# ProDoc_Custom_Keyboard_2025-10-23_RV1.net
KiCad netlist of a schematic drawn in EasyEDA Pro
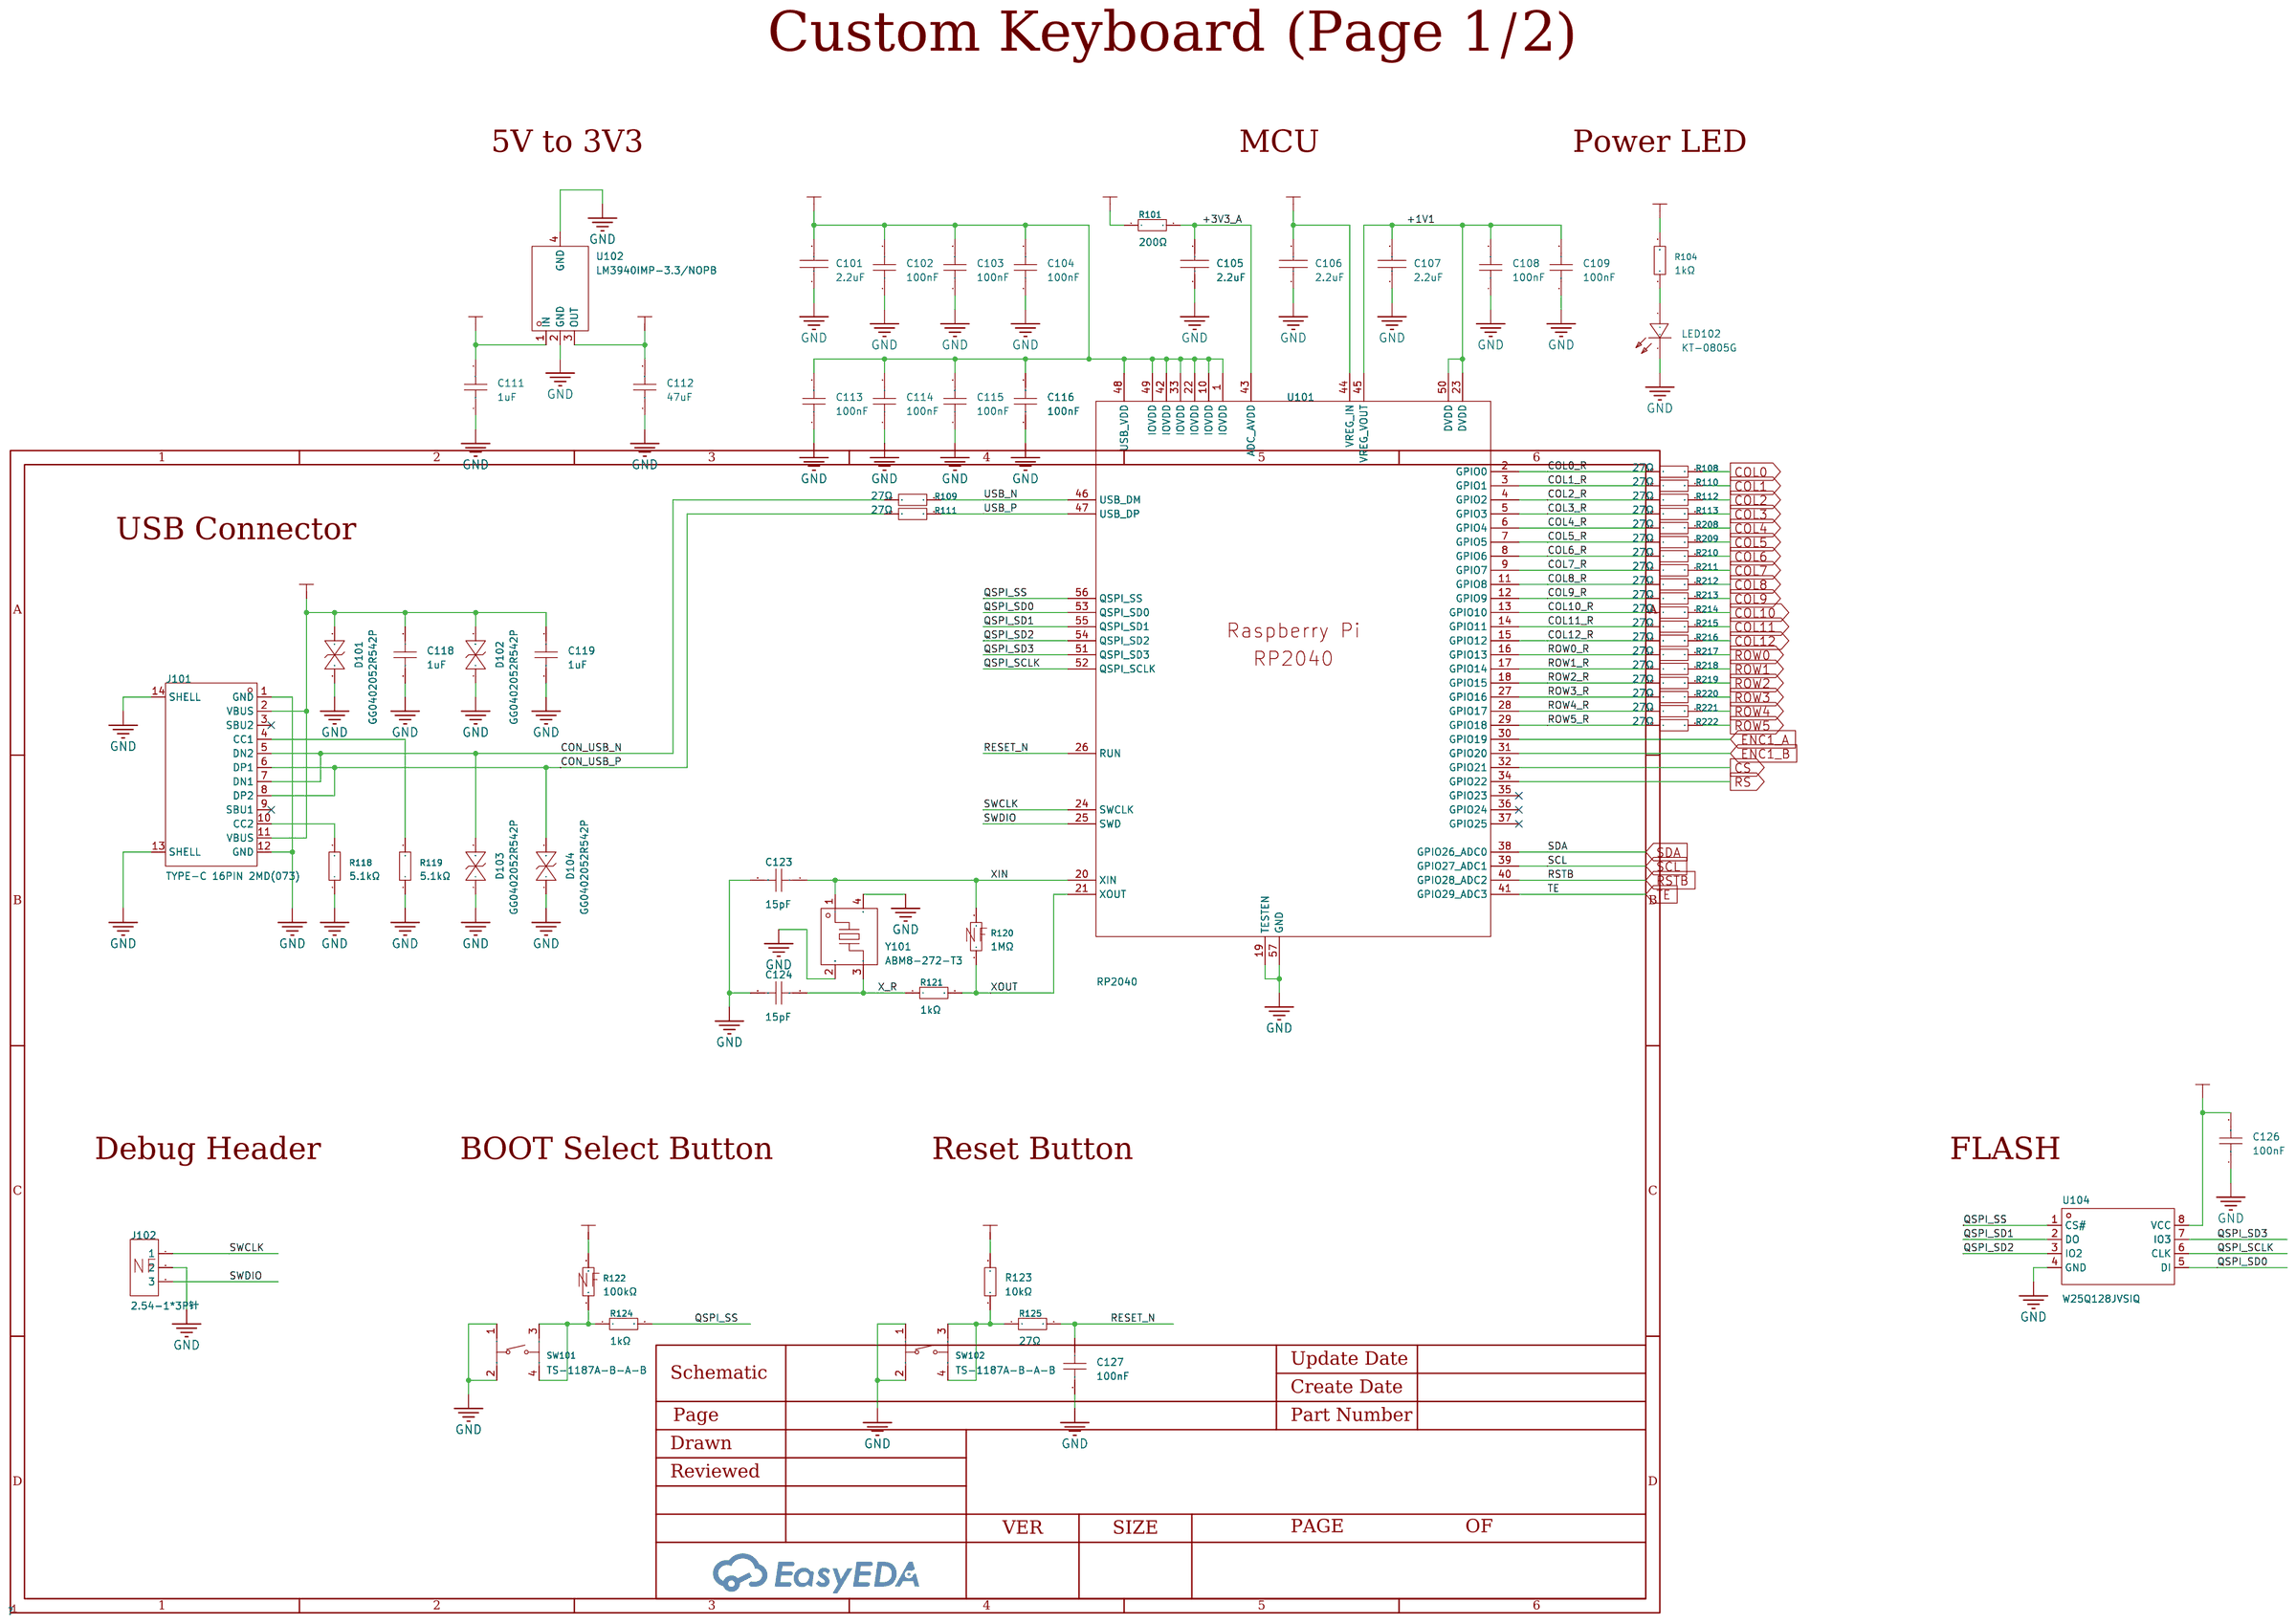
[diagram p0: MCU]
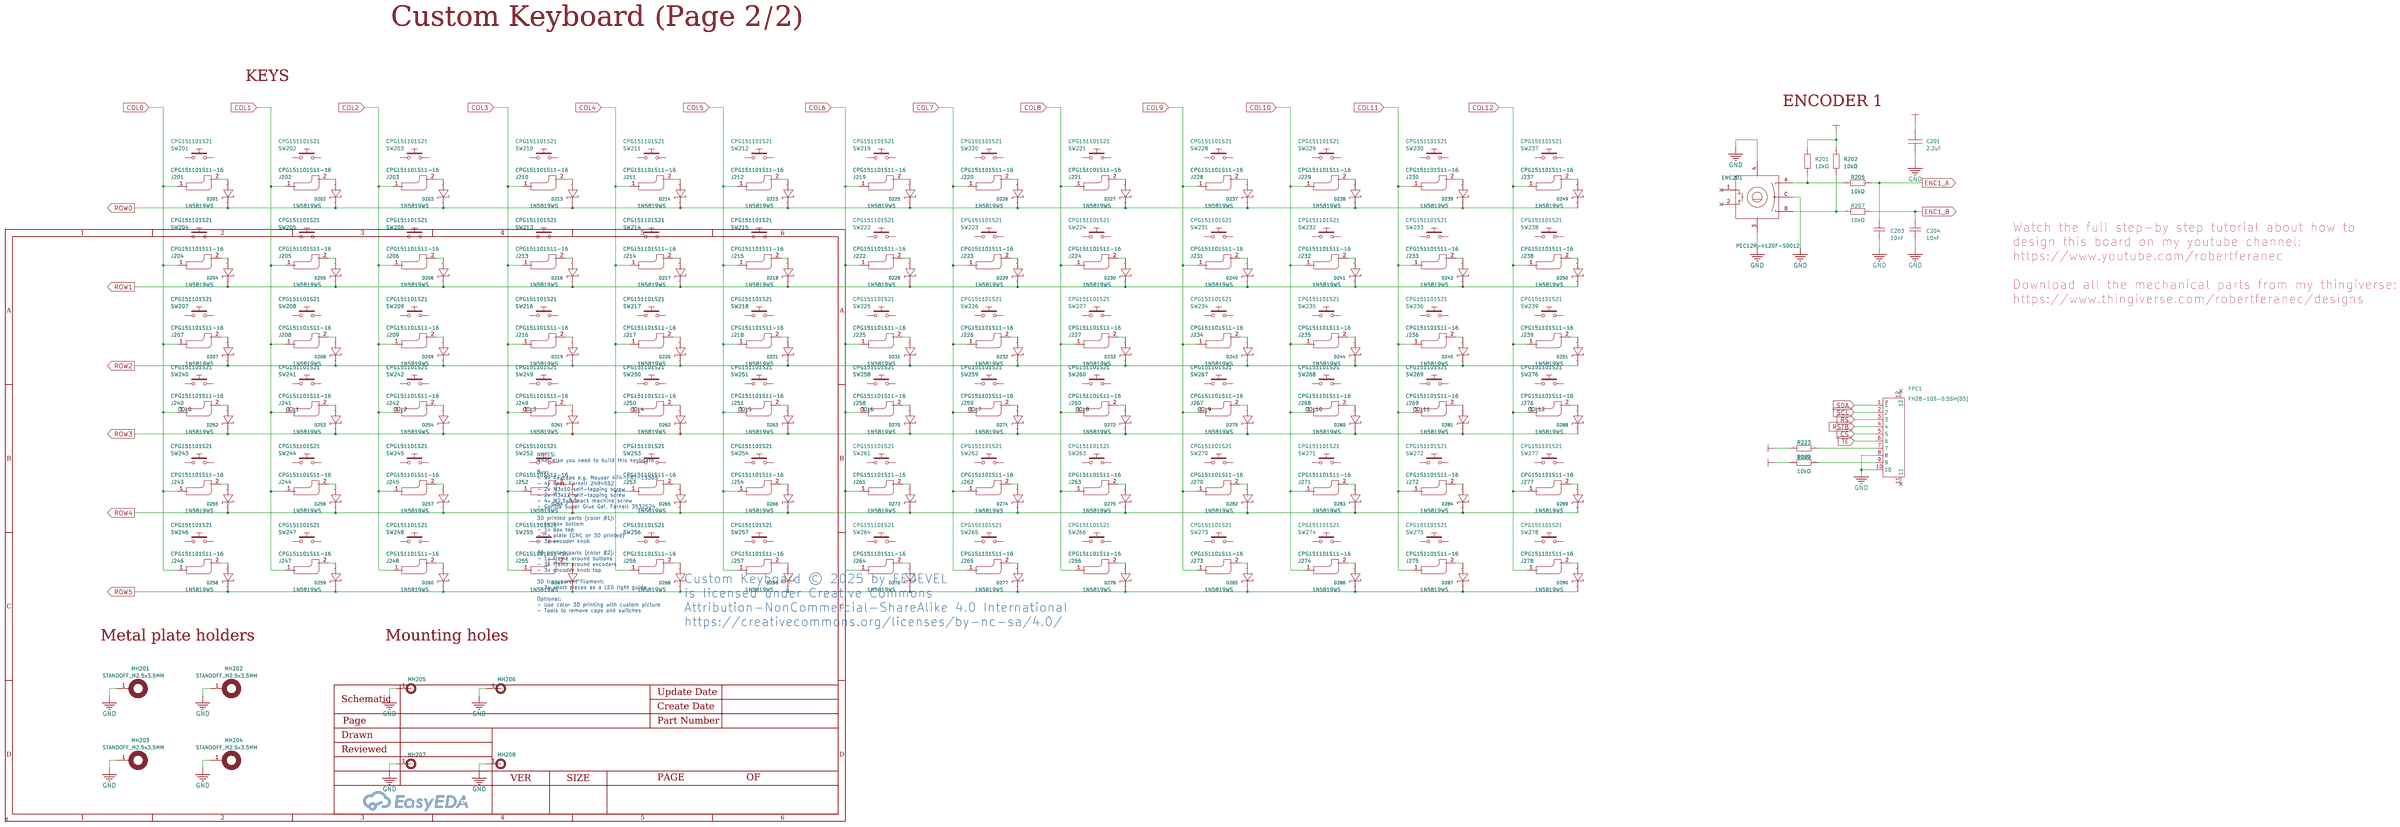
[diagram p1: OTHER]

(export (version "E")
  (design (tool "Eeschema 10.0.6"))
  (components
    (comp (ref "C101")
      (value "2.2uF")
      (footprint "easyedapro:C0402")
      (fields
        (field (name "Manufacturer Part") "CL05A225MQ5NSNC")
        (field (name "Manufacturer") "SAMSUNG(三星)")
      )
      (libsource (lib "easyedapro") (part "CL05A225MQ5NSNC"))
    )
    (comp (ref "C102")
      (value "100nF")
      (footprint "easyedapro:C0402")
      (fields
        (field (name "Manufacturer Part") "CL05B104KO5NNNC")
        (field (name "Manufacturer") "SAMSUNG(三星)")
      )
      (libsource (lib "easyedapro") (part "CL05B104KO5NNNC"))
    )
    (comp (ref "C103")
      (value "100nF")
      (footprint "easyedapro:C0402")
      (fields
        (field (name "Manufacturer Part") "CL05B104KO5NNNC")
        (field (name "Manufacturer") "SAMSUNG(三星)")
      )
      (libsource (lib "easyedapro") (part "CL05B104KO5NNNC"))
    )
    (comp (ref "C104")
      (value "100nF")
      (footprint "easyedapro:C0402")
      (fields
        (field (name "Manufacturer Part") "CL05B104KO5NNNC")
        (field (name "Manufacturer") "SAMSUNG(三星)")
      )
      (libsource (lib "easyedapro") (part "CL05B104KO5NNNC"))
    )
    (comp (ref "C105")
      (value "2.2uF")
      (footprint "easyedapro:C0402")
      (fields
        (field (name "Manufacturer Part") "CL05A225MQ5NSNC")
        (field (name "Manufacturer") "SAMSUNG(三星)")
      )
      (libsource (lib "easyedapro") (part "CL05A225MQ5NSNC"))
    )
    (comp (ref "C106")
      (value "2.2uF")
      (footprint "easyedapro:C0402")
      (fields
        (field (name "Manufacturer Part") "CL05A225MQ5NSNC")
        (field (name "Manufacturer") "SAMSUNG(三星)")
      )
      (libsource (lib "easyedapro") (part "CL05A225MQ5NSNC"))
    )
    (comp (ref "C107")
      (value "2.2uF")
      (footprint "easyedapro:C0402")
      (fields
        (field (name "Manufacturer Part") "CL05A225MQ5NSNC")
        (field (name "Manufacturer") "SAMSUNG(三星)")
      )
      (libsource (lib "easyedapro") (part "CL05A225MQ5NSNC"))
    )
    (comp (ref "C108")
      (value "100nF")
      (footprint "easyedapro:C0402")
      (fields
        (field (name "Manufacturer Part") "CL05B104KO5NNNC")
        (field (name "Manufacturer") "SAMSUNG(三星)")
      )
      (libsource (lib "easyedapro") (part "CL05B104KO5NNNC"))
    )
    (comp (ref "C109")
      (value "100nF")
      (footprint "easyedapro:C0402")
      (fields
        (field (name "Manufacturer Part") "CL05B104KO5NNNC")
        (field (name "Manufacturer") "SAMSUNG(三星)")
      )
      (libsource (lib "easyedapro") (part "CL05B104KO5NNNC"))
    )
    (comp (ref "C111")
      (value "1uF")
      (footprint "easyedapro:C0402")
      (fields
        (field (name "Manufacturer Part") "CL05A105KA5NQNC")
        (field (name "Manufacturer") "SAMSUNG(三星)")
      )
      (libsource (lib "easyedapro") (part "CL05A105KA5NQNC"))
    )
    (comp (ref "C112")
      (value "47uF")
      (footprint "easyedapro:C1206")
      (fields
        (field (name "Manufacturer Part") "CL31A476MPHNNNE")
        (field (name "Manufacturer") "SAMSUNG(三星)")
      )
      (libsource (lib "easyedapro") (part "CL31A476MPHNNNE"))
    )
    (comp (ref "C113")
      (value "100nF")
      (footprint "easyedapro:C0402")
      (fields
        (field (name "Manufacturer Part") "CL05B104KO5NNNC")
        (field (name "Manufacturer") "SAMSUNG(三星)")
      )
      (libsource (lib "easyedapro") (part "CL05B104KO5NNNC"))
    )
    (comp (ref "C114")
      (value "100nF")
      (footprint "easyedapro:C0402")
      (fields
        (field (name "Manufacturer Part") "CL05B104KO5NNNC")
        (field (name "Manufacturer") "SAMSUNG(三星)")
      )
      (libsource (lib "easyedapro") (part "CL05B104KO5NNNC"))
    )
    (comp (ref "C115")
      (value "100nF")
      (footprint "easyedapro:C0402")
      (fields
        (field (name "Manufacturer Part") "CL05B104KO5NNNC")
        (field (name "Manufacturer") "SAMSUNG(三星)")
      )
      (libsource (lib "easyedapro") (part "CL05B104KO5NNNC"))
    )
    (comp (ref "C116")
      (value "100nF")
      (footprint "easyedapro:C0402")
      (fields
        (field (name "Manufacturer Part") "CL05B104KO5NNNC")
        (field (name "Manufacturer") "SAMSUNG(三星)")
      )
      (libsource (lib "easyedapro") (part "CL05B104KO5NNNC"))
    )
    (comp (ref "C118")
      (value "1uF")
      (footprint "easyedapro:C0402")
      (fields
        (field (name "Manufacturer Part") "CL05A105KA5NQNC")
        (field (name "Manufacturer") "SAMSUNG(三星)")
      )
      (libsource (lib "easyedapro") (part "CL05A105KA5NQNC"))
    )
    (comp (ref "C119")
      (value "1uF")
      (footprint "easyedapro:C0402")
      (fields
        (field (name "Manufacturer Part") "CL05A105KA5NQNC")
        (field (name "Manufacturer") "SAMSUNG(三星)")
      )
      (libsource (lib "easyedapro") (part "CL05A105KA5NQNC"))
    )
    (comp (ref "C123")
      (value "15pF")
      (footprint "easyedapro:C0402")
      (fields
        (field (name "Manufacturer Part") "CL05C150JB5NNNC")
        (field (name "Manufacturer") "SAMSUNG(三星)")
      )
      (libsource (lib "easyedapro") (part "CL05C150JB5NNNC"))
    )
    (comp (ref "C124")
      (value "15pF")
      (footprint "easyedapro:C0402")
      (fields
        (field (name "Manufacturer Part") "CL05C150JB5NNNC")
        (field (name "Manufacturer") "SAMSUNG(三星)")
      )
      (libsource (lib "easyedapro") (part "CL05C150JB5NNNC"))
    )
    (comp (ref "C126")
      (value "100nF")
      (footprint "easyedapro:C0402")
      (fields
        (field (name "Manufacturer Part") "CL05B104KO5NNNC")
        (field (name "Manufacturer") "SAMSUNG(三星)")
      )
      (libsource (lib "easyedapro") (part "CL05B104KO5NNNC"))
    )
    (comp (ref "C127")
      (value "100nF")
      (footprint "easyedapro:C0402")
      (fields
        (field (name "Manufacturer Part") "CL05B104KO5NNNC")
        (field (name "Manufacturer") "SAMSUNG(三星)")
      )
      (libsource (lib "easyedapro") (part "CL05B104KO5NNNC"))
    )
    (comp (ref "D101")
      (value "GG0402052R542P")
      (footprint "easyedapro:D0402-BI")
      (fields (field (name "Manufacturer") "Kyocera AVX"))
      (libsource (lib "easyedapro") (part "GG0402052R542P"))
    )
    (comp (ref "D102")
      (value "GG0402052R542P")
      (footprint "easyedapro:D0402-BI")
      (fields (field (name "Manufacturer") "Kyocera AVX"))
      (libsource (lib "easyedapro") (part "GG0402052R542P"))
    )
    (comp (ref "D103")
      (value "GG0402052R542P")
      (footprint "easyedapro:D0402-BI")
      (fields (field (name "Manufacturer") "Kyocera AVX"))
      (libsource (lib "easyedapro") (part "GG0402052R542P"))
    )
    (comp (ref "D104")
      (value "GG0402052R542P")
      (footprint "easyedapro:D0402-BI")
      (fields (field (name "Manufacturer") "Kyocera AVX"))
      (libsource (lib "easyedapro") (part "GG0402052R542P"))
    )
    (comp (ref "J101")
      (value "TYPE-C 16PIN 2MD(073)")
      (footprint "easyedapro:USB-C-SMD_TYPE-C-6PIN-2MD-073")
      (fields (field (name "Manufacturer") "SHOU HAN(首韩)"))
      (libsource (lib "easyedapro") (part "TYPE-C 16PIN 2MD(073)"))
    )
    (comp (ref "J102")
      (value "2.54-1*3P针")
      (footprint "easyedapro:HDR-TH_3P-P2.54-V-M-1")
      (fields (field (name "Manufacturer") "BOOMELE(博穆精密)"))
      (libsource (lib "easyedapro") (part "Header-Male-2.54_1x3"))
    )
    (comp (ref "LED102")
      (value "KT-0805G")
      (footprint "easyedapro:LED0805-R-RD")
      (fields (field (name "Manufacturer") "KENTO"))
      (libsource (lib "easyedapro") (part "0805G (Green)"))
    )
    (comp (ref "R101")
      (value "200Ω")
      (footprint "easyedapro:R0402")
      (fields
        (field (name "Manufacturer Part") "0402WGF2000TCE")
        (field (name "Manufacturer") "UNI-ROYAL(厚声)")
      )
      (libsource (lib "easyedapro") (part "0402WGF2000TCE"))
    )
    (comp (ref "R104")
      (value "1kΩ")
      (footprint "easyedapro:R0402")
      (fields
        (field (name "Manufacturer Part") "0402WGF1001TCE")
        (field (name "Manufacturer") "UNI-ROYAL(厚声)")
      )
      (libsource (lib "easyedapro") (part "0402WGF1001TCE"))
    )
    (comp (ref "R108")
      (value "27Ω")
      (footprint "easyedapro:R0402")
      (fields
        (field (name "Manufacturer Part") "0402WGF270JTCE")
        (field (name "Manufacturer") "UNI-ROYAL(厚声)")
      )
      (libsource (lib "easyedapro") (part "0402WGF270JTCE"))
    )
    (comp (ref "R109")
      (value "27Ω")
      (footprint "easyedapro:R0402")
      (fields
        (field (name "Manufacturer Part") "0402WGF270JTCE")
        (field (name "Manufacturer") "UNI-ROYAL(厚声)")
      )
      (libsource (lib "easyedapro") (part "0402WGF270JTCE"))
    )
    (comp (ref "R110")
      (value "27Ω")
      (footprint "easyedapro:R0402")
      (fields
        (field (name "Manufacturer Part") "0402WGF270JTCE")
        (field (name "Manufacturer") "UNI-ROYAL(厚声)")
      )
      (libsource (lib "easyedapro") (part "0402WGF270JTCE"))
    )
    (comp (ref "R111")
      (value "27Ω")
      (footprint "easyedapro:R0402")
      (fields
        (field (name "Manufacturer Part") "0402WGF270JTCE")
        (field (name "Manufacturer") "UNI-ROYAL(厚声)")
      )
      (libsource (lib "easyedapro") (part "0402WGF270JTCE"))
    )
    (comp (ref "R112")
      (value "27Ω")
      (footprint "easyedapro:R0402")
      (fields
        (field (name "Manufacturer Part") "0402WGF270JTCE")
        (field (name "Manufacturer") "UNI-ROYAL(厚声)")
      )
      (libsource (lib "easyedapro") (part "0402WGF270JTCE"))
    )
    (comp (ref "R113")
      (value "27Ω")
      (footprint "easyedapro:R0402")
      (fields
        (field (name "Manufacturer Part") "0402WGF270JTCE")
        (field (name "Manufacturer") "UNI-ROYAL(厚声)")
      )
      (libsource (lib "easyedapro") (part "0402WGF270JTCE"))
    )
    (comp (ref "R118")
      (value "5.1kΩ")
      (footprint "easyedapro:R0402")
      (fields
        (field (name "Manufacturer Part") "0402WGF5101TCE")
        (field (name "Manufacturer") "UNI-ROYAL(厚声)")
      )
      (libsource (lib "easyedapro") (part "0402WGF5101TCE"))
    )
    (comp (ref "R119")
      (value "5.1kΩ")
      (footprint "easyedapro:R0402")
      (fields
        (field (name "Manufacturer Part") "0402WGF5101TCE")
        (field (name "Manufacturer") "UNI-ROYAL(厚声)")
      )
      (libsource (lib "easyedapro") (part "0402WGF5101TCE"))
    )
    (comp (ref "R120")
      (value "1MΩ")
      (footprint "easyedapro:R0402")
      (fields
        (field (name "Manufacturer Part") "0402WGF1004TCE")
        (field (name "Manufacturer") "UNI-ROYAL(厚声)")
      )
      (libsource (lib "easyedapro") (part "0402WGF1004TCE"))
    )
    (comp (ref "R121")
      (value "1kΩ")
      (footprint "easyedapro:R0402")
      (fields
        (field (name "Manufacturer Part") "0402WGF1001TCE")
        (field (name "Manufacturer") "UNI-ROYAL(厚声)")
      )
      (libsource (lib "easyedapro") (part "0402WGF1001TCE"))
    )
    (comp (ref "R122")
      (value "100kΩ")
      (footprint "easyedapro:R0402")
      (fields
        (field (name "Manufacturer Part") "0402WGF1003TCE")
        (field (name "Manufacturer") "UNI-ROYAL(厚声)")
      )
      (libsource (lib "easyedapro") (part "0402WGF1003TCE"))
    )
    (comp (ref "R123")
      (value "10kΩ")
      (footprint "easyedapro:R0402")
      (fields
        (field (name "Manufacturer Part") "0402WGF1002TCE")
        (field (name "Manufacturer") "UNI-ROYAL(厚声)")
      )
      (libsource (lib "easyedapro") (part "0402WGF1002TCE"))
    )
    (comp (ref "R124")
      (value "1kΩ")
      (footprint "easyedapro:R0402")
      (fields
        (field (name "Manufacturer Part") "0402WGF1001TCE")
        (field (name "Manufacturer") "UNI-ROYAL(厚声)")
      )
      (libsource (lib "easyedapro") (part "0402WGF1001TCE"))
    )
    (comp (ref "R125")
      (value "27Ω")
      (footprint "easyedapro:R0402")
      (fields
        (field (name "Manufacturer Part") "0402WGF270JTCE")
        (field (name "Manufacturer") "UNI-ROYAL(厚声)")
      )
      (libsource (lib "easyedapro") (part "0402WGF270JTCE"))
    )
    (comp (ref "R208")
      (value "27Ω")
      (footprint "easyedapro:R0402")
      (fields
        (field (name "Manufacturer Part") "0402WGF270JTCE")
        (field (name "Manufacturer") "UNI-ROYAL(厚声)")
      )
      (libsource (lib "easyedapro") (part "0402WGF270JTCE"))
    )
    (comp (ref "R209")
      (value "27Ω")
      (footprint "easyedapro:R0402")
      (fields
        (field (name "Manufacturer Part") "0402WGF270JTCE")
        (field (name "Manufacturer") "UNI-ROYAL(厚声)")
      )
      (libsource (lib "easyedapro") (part "0402WGF270JTCE"))
    )
    (comp (ref "R210")
      (value "27Ω")
      (footprint "easyedapro:R0402")
      (fields
        (field (name "Manufacturer Part") "0402WGF270JTCE")
        (field (name "Manufacturer") "UNI-ROYAL(厚声)")
      )
      (libsource (lib "easyedapro") (part "0402WGF270JTCE"))
    )
    (comp (ref "R211")
      (value "27Ω")
      (footprint "easyedapro:R0402")
      (fields
        (field (name "Manufacturer Part") "0402WGF270JTCE")
        (field (name "Manufacturer") "UNI-ROYAL(厚声)")
      )
      (libsource (lib "easyedapro") (part "0402WGF270JTCE"))
    )
    (comp (ref "R212")
      (value "27Ω")
      (footprint "easyedapro:R0402")
      (fields
        (field (name "Manufacturer Part") "0402WGF270JTCE")
        (field (name "Manufacturer") "UNI-ROYAL(厚声)")
      )
      (libsource (lib "easyedapro") (part "0402WGF270JTCE"))
    )
    (comp (ref "R213")
      (value "27Ω")
      (footprint "easyedapro:R0402")
      (fields
        (field (name "Manufacturer Part") "0402WGF270JTCE")
        (field (name "Manufacturer") "UNI-ROYAL(厚声)")
      )
      (libsource (lib "easyedapro") (part "0402WGF270JTCE"))
    )
    (comp (ref "R214")
      (value "27Ω")
      (footprint "easyedapro:R0402")
      (fields
        (field (name "Manufacturer Part") "0402WGF270JTCE")
        (field (name "Manufacturer") "UNI-ROYAL(厚声)")
      )
      (libsource (lib "easyedapro") (part "0402WGF270JTCE"))
    )
    (comp (ref "R215")
      (value "27Ω")
      (footprint "easyedapro:R0402")
      (fields
        (field (name "Manufacturer Part") "0402WGF270JTCE")
        (field (name "Manufacturer") "UNI-ROYAL(厚声)")
      )
      (libsource (lib "easyedapro") (part "0402WGF270JTCE"))
    )
    (comp (ref "R216")
      (value "27Ω")
      (footprint "easyedapro:R0402")
      (fields
        (field (name "Manufacturer Part") "0402WGF270JTCE")
        (field (name "Manufacturer") "UNI-ROYAL(厚声)")
      )
      (libsource (lib "easyedapro") (part "0402WGF270JTCE"))
    )
    (comp (ref "R217")
      (value "27Ω")
      (footprint "easyedapro:R0402")
      (fields
        (field (name "Manufacturer Part") "0402WGF270JTCE")
        (field (name "Manufacturer") "UNI-ROYAL(厚声)")
      )
      (libsource (lib "easyedapro") (part "0402WGF270JTCE"))
    )
    (comp (ref "R218")
      (value "27Ω")
      (footprint "easyedapro:R0402")
      (fields
        (field (name "Manufacturer Part") "0402WGF270JTCE")
        (field (name "Manufacturer") "UNI-ROYAL(厚声)")
      )
      (libsource (lib "easyedapro") (part "0402WGF270JTCE"))
    )
    (comp (ref "R219")
      (value "27Ω")
      (footprint "easyedapro:R0402")
      (fields
        (field (name "Manufacturer Part") "0402WGF270JTCE")
        (field (name "Manufacturer") "UNI-ROYAL(厚声)")
      )
      (libsource (lib "easyedapro") (part "0402WGF270JTCE"))
    )
    (comp (ref "R220")
      (value "27Ω")
      (footprint "easyedapro:R0402")
      (fields
        (field (name "Manufacturer Part") "0402WGF270JTCE")
        (field (name "Manufacturer") "UNI-ROYAL(厚声)")
      )
      (libsource (lib "easyedapro") (part "0402WGF270JTCE"))
    )
    (comp (ref "R221")
      (value "27Ω")
      (footprint "easyedapro:R0402")
      (fields
        (field (name "Manufacturer Part") "0402WGF270JTCE")
        (field (name "Manufacturer") "UNI-ROYAL(厚声)")
      )
      (libsource (lib "easyedapro") (part "0402WGF270JTCE"))
    )
    (comp (ref "R222")
      (value "27Ω")
      (footprint "easyedapro:R0402")
      (fields
        (field (name "Manufacturer Part") "0402WGF270JTCE")
        (field (name "Manufacturer") "UNI-ROYAL(厚声)")
      )
      (libsource (lib "easyedapro") (part "0402WGF270JTCE"))
    )
    (comp (ref "SW101")
      (value "TS-1187A-B-A-B")
      (footprint "easyedapro:SW-SMD_4P-L5.1-W5.1-P3.70-LS6.5-TL-2")
      (fields (field (name "Manufacturer") "XKB Connectivity(中国星坤)"))
      (libsource (lib "easyedapro") (part "TS-1187A-B-A-B"))
    )
    (comp (ref "SW102")
      (value "TS-1187A-B-A-B")
      (footprint "easyedapro:SW-SMD_4P-L5.1-W5.1-P3.70-LS6.5-TL-2")
      (fields (field (name "Manufacturer") "XKB Connectivity(中国星坤)"))
      (libsource (lib "easyedapro") (part "TS-1187A-B-A-B"))
    )
    (comp (ref "U101")
      (value "RP2040")
      (footprint "easyedapro:LQFN-56_L7.0-W7.0-P0.4-EP_1")
      (fields (field (name "Manufacturer") "Raspberry Pi(树莓派)"))
      (libsource (lib "easyedapro") (part "RP2040_C2040_RF_v1.0"))
    )
    (comp (ref "U102")
      (value "LM3940IMP-3.3/NOPB")
      (footprint "easyedapro:SOT-223_L6.5-W3.5-P2.30-LS7.0-BR")
      (fields (field (name "Manufacturer") "TI(德州仪器)"))
      (libsource (lib "easyedapro") (part "LM3940IMP-3.3/NOPB"))
    )
    (comp (ref "U104")
      (value "W25Q128JVSIQ")
      (footprint "easyedapro:SOIC-8_L5.3-W5.3-P1.27-LS8.0-BL")
      (fields (field (name "Manufacturer") "WINBOND(华邦)"))
      (libsource (lib "easyedapro") (part "W25Q128JVSIQTR"))
    )
    (comp (ref "Y101")
      (value "ABM8-272-T3")
      (footprint "easyedapro:CRYSTAL-SMD_4P-L3.2-W2.5-BL")
      (fields (field (name "Manufacturer") "ABRACON"))
      (libsource (lib "easyedapro") (part "ABM8-272-T3_C20625731"))
    )
    (comp (ref "C201")
      (value "2.2uF")
      (footprint "easyedapro:C0402")
      (fields
        (field (name "Manufacturer Part") "CL05A225MQ5NSNC")
        (field (name "Manufacturer") "SAMSUNG(三星)")
      )
      (libsource (lib "easyedapro") (part "CL05A225MQ5NSNC"))
    )
    (comp (ref "C203")
      (value "10nF")
      (footprint "easyedapro:C0402")
      (fields
        (field (name "Manufacturer Part") "CL05B103KB5NNNC")
        (field (name "Manufacturer") "SAMSUNG(三星)")
      )
      (libsource (lib "easyedapro") (part "CL05B103KB5NNNC"))
    )
    (comp (ref "C204")
      (value "10nF")
      (footprint "easyedapro:C0402")
      (fields
        (field (name "Manufacturer Part") "CL05B103KB5NNNC")
        (field (name "Manufacturer") "SAMSUNG(三星)")
      )
      (libsource (lib "easyedapro") (part "CL05B103KB5NNNC"))
    )
    (comp (ref "D201")
      (value "1N5819WS")
      (footprint "easyedapro:SOD-323_L1.8-W1.3-LS2.5-RD")
      (description "Forward Voltage (Vf@If):600mV@1A Reverse Voltage (Vr):40V Average Rectified Current (Io):1A")
      (fields (field (name "Manufacturer") "Hottech(合科泰)"))
      (libsource (lib "easyedapro") (part "1N5819WS"))
    )
    (comp (ref "D202")
      (value "1N5819WS")
      (footprint "easyedapro:SOD-323_L1.8-W1.3-LS2.5-RD")
      (description "Forward Voltage (Vf@If):600mV@1A Reverse Voltage (Vr):40V Average Rectified Current (Io):1A")
      (fields (field (name "Manufacturer") "Hottech(合科泰)"))
      (libsource (lib "easyedapro") (part "1N5819WS"))
    )
    (comp (ref "D203")
      (value "1N5819WS")
      (footprint "easyedapro:SOD-323_L1.8-W1.3-LS2.5-RD")
      (description "Forward Voltage (Vf@If):600mV@1A Reverse Voltage (Vr):40V Average Rectified Current (Io):1A")
      (fields (field (name "Manufacturer") "Hottech(合科泰)"))
      (libsource (lib "easyedapro") (part "1N5819WS"))
    )
    (comp (ref "D204")
      (value "1N5819WS")
      (footprint "easyedapro:SOD-323_L1.8-W1.3-LS2.5-RD")
      (description "Forward Voltage (Vf@If):600mV@1A Reverse Voltage (Vr):40V Average Rectified Current (Io):1A")
      (fields (field (name "Manufacturer") "Hottech(合科泰)"))
      (libsource (lib "easyedapro") (part "1N5819WS"))
    )
    (comp (ref "D205")
      (value "1N5819WS")
      (footprint "easyedapro:SOD-323_L1.8-W1.3-LS2.5-RD")
      (description "Forward Voltage (Vf@If):600mV@1A Reverse Voltage (Vr):40V Average Rectified Current (Io):1A")
      (fields (field (name "Manufacturer") "Hottech(合科泰)"))
      (libsource (lib "easyedapro") (part "1N5819WS"))
    )
    (comp (ref "D206")
      (value "1N5819WS")
      (footprint "easyedapro:SOD-323_L1.8-W1.3-LS2.5-RD")
      (description "Forward Voltage (Vf@If):600mV@1A Reverse Voltage (Vr):40V Average Rectified Current (Io):1A")
      (fields (field (name "Manufacturer") "Hottech(合科泰)"))
      (libsource (lib "easyedapro") (part "1N5819WS"))
    )
    (comp (ref "D207")
      (value "1N5819WS")
      (footprint "easyedapro:SOD-323_L1.8-W1.3-LS2.5-RD")
      (description "Forward Voltage (Vf@If):600mV@1A Reverse Voltage (Vr):40V Average Rectified Current (Io):1A")
      (fields (field (name "Manufacturer") "Hottech(合科泰)"))
      (libsource (lib "easyedapro") (part "1N5819WS"))
    )
    (comp (ref "D208")
      (value "1N5819WS")
      (footprint "easyedapro:SOD-323_L1.8-W1.3-LS2.5-RD")
      (description "Forward Voltage (Vf@If):600mV@1A Reverse Voltage (Vr):40V Average Rectified Current (Io):1A")
      (fields (field (name "Manufacturer") "Hottech(合科泰)"))
      (libsource (lib "easyedapro") (part "1N5819WS"))
    )
    (comp (ref "D209")
      (value "1N5819WS")
      (footprint "easyedapro:SOD-323_L1.8-W1.3-LS2.5-RD")
      (description "Forward Voltage (Vf@If):600mV@1A Reverse Voltage (Vr):40V Average Rectified Current (Io):1A")
      (fields (field (name "Manufacturer") "Hottech(合科泰)"))
      (libsource (lib "easyedapro") (part "1N5819WS"))
    )
    (comp (ref "D213")
      (value "1N5819WS")
      (footprint "easyedapro:SOD-323_L1.8-W1.3-LS2.5-RD")
      (description "Forward Voltage (Vf@If):600mV@1A Reverse Voltage (Vr):40V Average Rectified Current (Io):1A")
      (fields (field (name "Manufacturer") "Hottech(合科泰)"))
      (libsource (lib "easyedapro") (part "1N5819WS"))
    )
    (comp (ref "D214")
      (value "1N5819WS")
      (footprint "easyedapro:SOD-323_L1.8-W1.3-LS2.5-RD")
      (description "Forward Voltage (Vf@If):600mV@1A Reverse Voltage (Vr):40V Average Rectified Current (Io):1A")
      (fields (field (name "Manufacturer") "Hottech(合科泰)"))
      (libsource (lib "easyedapro") (part "1N5819WS"))
    )
    (comp (ref "D215")
      (value "1N5819WS")
      (footprint "easyedapro:SOD-323_L1.8-W1.3-LS2.5-RD")
      (description "Forward Voltage (Vf@If):600mV@1A Reverse Voltage (Vr):40V Average Rectified Current (Io):1A")
      (fields (field (name "Manufacturer") "Hottech(合科泰)"))
      (libsource (lib "easyedapro") (part "1N5819WS"))
    )
    (comp (ref "D216")
      (value "1N5819WS")
      (footprint "easyedapro:SOD-323_L1.8-W1.3-LS2.5-RD")
      (description "Forward Voltage (Vf@If):600mV@1A Reverse Voltage (Vr):40V Average Rectified Current (Io):1A")
      (fields (field (name "Manufacturer") "Hottech(合科泰)"))
      (libsource (lib "easyedapro") (part "1N5819WS"))
    )
    (comp (ref "D217")
      (value "1N5819WS")
      (footprint "easyedapro:SOD-323_L1.8-W1.3-LS2.5-RD")
      (description "Forward Voltage (Vf@If):600mV@1A Reverse Voltage (Vr):40V Average Rectified Current (Io):1A")
      (fields (field (name "Manufacturer") "Hottech(合科泰)"))
      (libsource (lib "easyedapro") (part "1N5819WS"))
    )
    (comp (ref "D218")
      (value "1N5819WS")
      (footprint "easyedapro:SOD-323_L1.8-W1.3-LS2.5-RD")
      (description "Forward Voltage (Vf@If):600mV@1A Reverse Voltage (Vr):40V Average Rectified Current (Io):1A")
      (fields (field (name "Manufacturer") "Hottech(合科泰)"))
      (libsource (lib "easyedapro") (part "1N5819WS"))
    )
    (comp (ref "D219")
      (value "1N5819WS")
      (footprint "easyedapro:SOD-323_L1.8-W1.3-LS2.5-RD")
      (description "Forward Voltage (Vf@If):600mV@1A Reverse Voltage (Vr):40V Average Rectified Current (Io):1A")
      (fields (field (name "Manufacturer") "Hottech(合科泰)"))
      (libsource (lib "easyedapro") (part "1N5819WS"))
    )
    (comp (ref "D220")
      (value "1N5819WS")
      (footprint "easyedapro:SOD-323_L1.8-W1.3-LS2.5-RD")
      (description "Forward Voltage (Vf@If):600mV@1A Reverse Voltage (Vr):40V Average Rectified Current (Io):1A")
      (fields (field (name "Manufacturer") "Hottech(合科泰)"))
      (libsource (lib "easyedapro") (part "1N5819WS"))
    )
    (comp (ref "D221")
      (value "1N5819WS")
      (footprint "easyedapro:SOD-323_L1.8-W1.3-LS2.5-RD")
      (description "Forward Voltage (Vf@If):600mV@1A Reverse Voltage (Vr):40V Average Rectified Current (Io):1A")
      (fields (field (name "Manufacturer") "Hottech(合科泰)"))
      (libsource (lib "easyedapro") (part "1N5819WS"))
    )
    (comp (ref "D225")
      (value "1N5819WS")
      (footprint "easyedapro:SOD-323_L1.8-W1.3-LS2.5-RD")
      (description "Forward Voltage (Vf@If):600mV@1A Reverse Voltage (Vr):40V Average Rectified Current (Io):1A")
      (fields (field (name "Manufacturer") "Hottech(合科泰)"))
      (libsource (lib "easyedapro") (part "1N5819WS"))
    )
    (comp (ref "D226")
      (value "1N5819WS")
      (footprint "easyedapro:SOD-323_L1.8-W1.3-LS2.5-RD")
      (description "Forward Voltage (Vf@If):600mV@1A Reverse Voltage (Vr):40V Average Rectified Current (Io):1A")
      (fields (field (name "Manufacturer") "Hottech(合科泰)"))
      (libsource (lib "easyedapro") (part "1N5819WS"))
    )
    (comp (ref "D227")
      (value "1N5819WS")
      (footprint "easyedapro:SOD-323_L1.8-W1.3-LS2.5-RD")
      (description "Forward Voltage (Vf@If):600mV@1A Reverse Voltage (Vr):40V Average Rectified Current (Io):1A")
      (fields (field (name "Manufacturer") "Hottech(合科泰)"))
      (libsource (lib "easyedapro") (part "1N5819WS"))
    )
    (comp (ref "D228")
      (value "1N5819WS")
      (footprint "easyedapro:SOD-323_L1.8-W1.3-LS2.5-RD")
      (description "Forward Voltage (Vf@If):600mV@1A Reverse Voltage (Vr):40V Average Rectified Current (Io):1A")
      (fields (field (name "Manufacturer") "Hottech(合科泰)"))
      (libsource (lib "easyedapro") (part "1N5819WS"))
    )
    (comp (ref "D229")
      (value "1N5819WS")
      (footprint "easyedapro:SOD-323_L1.8-W1.3-LS2.5-RD")
      (description "Forward Voltage (Vf@If):600mV@1A Reverse Voltage (Vr):40V Average Rectified Current (Io):1A")
      (fields (field (name "Manufacturer") "Hottech(合科泰)"))
      (libsource (lib "easyedapro") (part "1N5819WS"))
    )
    (comp (ref "D230")
      (value "1N5819WS")
      (footprint "easyedapro:SOD-323_L1.8-W1.3-LS2.5-RD")
      (description "Forward Voltage (Vf@If):600mV@1A Reverse Voltage (Vr):40V Average Rectified Current (Io):1A")
      (fields (field (name "Manufacturer") "Hottech(合科泰)"))
      (libsource (lib "easyedapro") (part "1N5819WS"))
    )
    (comp (ref "D231")
      (value "1N5819WS")
      (footprint "easyedapro:SOD-323_L1.8-W1.3-LS2.5-RD")
      (description "Forward Voltage (Vf@If):600mV@1A Reverse Voltage (Vr):40V Average Rectified Current (Io):1A")
      (fields (field (name "Manufacturer") "Hottech(合科泰)"))
      (libsource (lib "easyedapro") (part "1N5819WS"))
    )
    (comp (ref "D232")
      (value "1N5819WS")
      (footprint "easyedapro:SOD-323_L1.8-W1.3-LS2.5-RD")
      (description "Forward Voltage (Vf@If):600mV@1A Reverse Voltage (Vr):40V Average Rectified Current (Io):1A")
      (fields (field (name "Manufacturer") "Hottech(合科泰)"))
      (libsource (lib "easyedapro") (part "1N5819WS"))
    )
    (comp (ref "D233")
      (value "1N5819WS")
      (footprint "easyedapro:SOD-323_L1.8-W1.3-LS2.5-RD")
      (description "Forward Voltage (Vf@If):600mV@1A Reverse Voltage (Vr):40V Average Rectified Current (Io):1A")
      (fields (field (name "Manufacturer") "Hottech(合科泰)"))
      (libsource (lib "easyedapro") (part "1N5819WS"))
    )
    (comp (ref "D237")
      (value "1N5819WS")
      (footprint "easyedapro:SOD-323_L1.8-W1.3-LS2.5-RD")
      (description "Forward Voltage (Vf@If):600mV@1A Reverse Voltage (Vr):40V Average Rectified Current (Io):1A")
      (fields (field (name "Manufacturer") "Hottech(合科泰)"))
      (libsource (lib "easyedapro") (part "1N5819WS"))
    )
    (comp (ref "D238")
      (value "1N5819WS")
      (footprint "easyedapro:SOD-323_L1.8-W1.3-LS2.5-RD")
      (description "Forward Voltage (Vf@If):600mV@1A Reverse Voltage (Vr):40V Average Rectified Current (Io):1A")
      (fields (field (name "Manufacturer") "Hottech(合科泰)"))
      (libsource (lib "easyedapro") (part "1N5819WS"))
    )
    (comp (ref "D239")
      (value "1N5819WS")
      (footprint "easyedapro:SOD-323_L1.8-W1.3-LS2.5-RD")
      (description "Forward Voltage (Vf@If):600mV@1A Reverse Voltage (Vr):40V Average Rectified Current (Io):1A")
      (fields (field (name "Manufacturer") "Hottech(合科泰)"))
      (libsource (lib "easyedapro") (part "1N5819WS"))
    )
    (comp (ref "D240")
      (value "1N5819WS")
      (footprint "easyedapro:SOD-323_L1.8-W1.3-LS2.5-RD")
      (description "Forward Voltage (Vf@If):600mV@1A Reverse Voltage (Vr):40V Average Rectified Current (Io):1A")
      (fields (field (name "Manufacturer") "Hottech(合科泰)"))
      (libsource (lib "easyedapro") (part "1N5819WS"))
    )
    (comp (ref "D241")
      (value "1N5819WS")
      (footprint "easyedapro:SOD-323_L1.8-W1.3-LS2.5-RD")
      (description "Forward Voltage (Vf@If):600mV@1A Reverse Voltage (Vr):40V Average Rectified Current (Io):1A")
      (fields (field (name "Manufacturer") "Hottech(合科泰)"))
      (libsource (lib "easyedapro") (part "1N5819WS"))
    )
    (comp (ref "D242")
      (value "1N5819WS")
      (footprint "easyedapro:SOD-323_L1.8-W1.3-LS2.5-RD")
      (description "Forward Voltage (Vf@If):600mV@1A Reverse Voltage (Vr):40V Average Rectified Current (Io):1A")
      (fields (field (name "Manufacturer") "Hottech(合科泰)"))
      (libsource (lib "easyedapro") (part "1N5819WS"))
    )
    (comp (ref "D243")
      (value "1N5819WS")
      (footprint "easyedapro:SOD-323_L1.8-W1.3-LS2.5-RD")
      (description "Forward Voltage (Vf@If):600mV@1A Reverse Voltage (Vr):40V Average Rectified Current (Io):1A")
      (fields (field (name "Manufacturer") "Hottech(合科泰)"))
      (libsource (lib "easyedapro") (part "1N5819WS"))
    )
    (comp (ref "D244")
      (value "1N5819WS")
      (footprint "easyedapro:SOD-323_L1.8-W1.3-LS2.5-RD")
      (description "Forward Voltage (Vf@If):600mV@1A Reverse Voltage (Vr):40V Average Rectified Current (Io):1A")
      (fields (field (name "Manufacturer") "Hottech(合科泰)"))
      (libsource (lib "easyedapro") (part "1N5819WS"))
    )
    (comp (ref "D245")
      (value "1N5819WS")
      (footprint "easyedapro:SOD-323_L1.8-W1.3-LS2.5-RD")
      (description "Forward Voltage (Vf@If):600mV@1A Reverse Voltage (Vr):40V Average Rectified Current (Io):1A")
      (fields (field (name "Manufacturer") "Hottech(合科泰)"))
      (libsource (lib "easyedapro") (part "1N5819WS"))
    )
    (comp (ref "D249")
      (value "1N5819WS")
      (footprint "easyedapro:SOD-323_L1.8-W1.3-LS2.5-RD")
      (description "Forward Voltage (Vf@If):600mV@1A Reverse Voltage (Vr):40V Average Rectified Current (Io):1A")
      (fields (field (name "Manufacturer") "Hottech(合科泰)"))
      (libsource (lib "easyedapro") (part "1N5819WS"))
    )
    (comp (ref "D250")
      (value "1N5819WS")
      (footprint "easyedapro:SOD-323_L1.8-W1.3-LS2.5-RD")
      (description "Forward Voltage (Vf@If):600mV@1A Reverse Voltage (Vr):40V Average Rectified Current (Io):1A")
      (fields (field (name "Manufacturer") "Hottech(合科泰)"))
      (libsource (lib "easyedapro") (part "1N5819WS"))
    )
    (comp (ref "D251")
      (value "1N5819WS")
      (footprint "easyedapro:SOD-323_L1.8-W1.3-LS2.5-RD")
      (description "Forward Voltage (Vf@If):600mV@1A Reverse Voltage (Vr):40V Average Rectified Current (Io):1A")
      (fields (field (name "Manufacturer") "Hottech(合科泰)"))
      (libsource (lib "easyedapro") (part "1N5819WS"))
    )
    (comp (ref "D252")
      (value "1N5819WS")
      (footprint "easyedapro:SOD-323_L1.8-W1.3-LS2.5-RD")
      (description "Forward Voltage (Vf@If):600mV@1A Reverse Voltage (Vr):40V Average Rectified Current (Io):1A")
      (fields (field (name "Manufacturer") "Hottech(合科泰)"))
      (libsource (lib "easyedapro") (part "1N5819WS"))
    )
    (comp (ref "D253")
      (value "1N5819WS")
      (footprint "easyedapro:SOD-323_L1.8-W1.3-LS2.5-RD")
      (description "Forward Voltage (Vf@If):600mV@1A Reverse Voltage (Vr):40V Average Rectified Current (Io):1A")
      (fields (field (name "Manufacturer") "Hottech(合科泰)"))
      (libsource (lib "easyedapro") (part "1N5819WS"))
    )
    (comp (ref "D254")
      (value "1N5819WS")
      (footprint "easyedapro:SOD-323_L1.8-W1.3-LS2.5-RD")
      (description "Forward Voltage (Vf@If):600mV@1A Reverse Voltage (Vr):40V Average Rectified Current (Io):1A")
      (fields (field (name "Manufacturer") "Hottech(合科泰)"))
      (libsource (lib "easyedapro") (part "1N5819WS"))
    )
    (comp (ref "D255")
      (value "1N5819WS")
      (footprint "easyedapro:SOD-323_L1.8-W1.3-LS2.5-RD")
      (description "Forward Voltage (Vf@If):600mV@1A Reverse Voltage (Vr):40V Average Rectified Current (Io):1A")
      (fields (field (name "Manufacturer") "Hottech(合科泰)"))
      (libsource (lib "easyedapro") (part "1N5819WS"))
    )
    (comp (ref "D256")
      (value "1N5819WS")
      (footprint "easyedapro:SOD-323_L1.8-W1.3-LS2.5-RD")
      (description "Forward Voltage (Vf@If):600mV@1A Reverse Voltage (Vr):40V Average Rectified Current (Io):1A")
      (fields (field (name "Manufacturer") "Hottech(合科泰)"))
      (libsource (lib "easyedapro") (part "1N5819WS"))
    )
    (comp (ref "D257")
      (value "1N5819WS")
      (footprint "easyedapro:SOD-323_L1.8-W1.3-LS2.5-RD")
      (description "Forward Voltage (Vf@If):600mV@1A Reverse Voltage (Vr):40V Average Rectified Current (Io):1A")
      (fields (field (name "Manufacturer") "Hottech(合科泰)"))
      (libsource (lib "easyedapro") (part "1N5819WS"))
    )
    (comp (ref "D258")
      (value "1N5819WS")
      (footprint "easyedapro:SOD-323_L1.8-W1.3-LS2.5-RD")
      (description "Forward Voltage (Vf@If):600mV@1A Reverse Voltage (Vr):40V Average Rectified Current (Io):1A")
      (fields (field (name "Manufacturer") "Hottech(合科泰)"))
      (libsource (lib "easyedapro") (part "1N5819WS"))
    )
    (comp (ref "D259")
      (value "1N5819WS")
      (footprint "easyedapro:SOD-323_L1.8-W1.3-LS2.5-RD")
      (description "Forward Voltage (Vf@If):600mV@1A Reverse Voltage (Vr):40V Average Rectified Current (Io):1A")
      (fields (field (name "Manufacturer") "Hottech(合科泰)"))
      (libsource (lib "easyedapro") (part "1N5819WS"))
    )
    (comp (ref "D260")
      (value "1N5819WS")
      (footprint "easyedapro:SOD-323_L1.8-W1.3-LS2.5-RD")
      (description "Forward Voltage (Vf@If):600mV@1A Reverse Voltage (Vr):40V Average Rectified Current (Io):1A")
      (fields (field (name "Manufacturer") "Hottech(合科泰)"))
      (libsource (lib "easyedapro") (part "1N5819WS"))
    )
    (comp (ref "D261")
      (value "1N5819WS")
      (footprint "easyedapro:SOD-323_L1.8-W1.3-LS2.5-RD")
      (description "Forward Voltage (Vf@If):600mV@1A Reverse Voltage (Vr):40V Average Rectified Current (Io):1A")
      (fields (field (name "Manufacturer") "Hottech(合科泰)"))
      (libsource (lib "easyedapro") (part "1N5819WS"))
    )
    (comp (ref "D262")
      (value "1N5819WS")
      (footprint "easyedapro:SOD-323_L1.8-W1.3-LS2.5-RD")
      (description "Forward Voltage (Vf@If):600mV@1A Reverse Voltage (Vr):40V Average Rectified Current (Io):1A")
      (fields (field (name "Manufacturer") "Hottech(合科泰)"))
      (libsource (lib "easyedapro") (part "1N5819WS"))
    )
    (comp (ref "D263")
      (value "1N5819WS")
      (footprint "easyedapro:SOD-323_L1.8-W1.3-LS2.5-RD")
      (description "Forward Voltage (Vf@If):600mV@1A Reverse Voltage (Vr):40V Average Rectified Current (Io):1A")
      (fields (field (name "Manufacturer") "Hottech(合科泰)"))
      (libsource (lib "easyedapro") (part "1N5819WS"))
    )
    (comp (ref "D264")
      (value "1N5819WS")
      (footprint "easyedapro:SOD-323_L1.8-W1.3-LS2.5-RD")
      (description "Forward Voltage (Vf@If):600mV@1A Reverse Voltage (Vr):40V Average Rectified Current (Io):1A")
      (fields (field (name "Manufacturer") "Hottech(合科泰)"))
      (libsource (lib "easyedapro") (part "1N5819WS"))
    )
    (comp (ref "D265")
      (value "1N5819WS")
      (footprint "easyedapro:SOD-323_L1.8-W1.3-LS2.5-RD")
      (description "Forward Voltage (Vf@If):600mV@1A Reverse Voltage (Vr):40V Average Rectified Current (Io):1A")
      (fields (field (name "Manufacturer") "Hottech(合科泰)"))
      (libsource (lib "easyedapro") (part "1N5819WS"))
    )
    (comp (ref "D266")
      (value "1N5819WS")
      (footprint "easyedapro:SOD-323_L1.8-W1.3-LS2.5-RD")
      (description "Forward Voltage (Vf@If):600mV@1A Reverse Voltage (Vr):40V Average Rectified Current (Io):1A")
      (fields (field (name "Manufacturer") "Hottech(合科泰)"))
      (libsource (lib "easyedapro") (part "1N5819WS"))
    )
    (comp (ref "D267")
      (value "1N5819WS")
      (footprint "easyedapro:SOD-323_L1.8-W1.3-LS2.5-RD")
      (description "Forward Voltage (Vf@If):600mV@1A Reverse Voltage (Vr):40V Average Rectified Current (Io):1A")
      (fields (field (name "Manufacturer") "Hottech(合科泰)"))
      (libsource (lib "easyedapro") (part "1N5819WS"))
    )
    (comp (ref "D268")
      (value "1N5819WS")
      (footprint "easyedapro:SOD-323_L1.8-W1.3-LS2.5-RD")
      (description "Forward Voltage (Vf@If):600mV@1A Reverse Voltage (Vr):40V Average Rectified Current (Io):1A")
      (fields (field (name "Manufacturer") "Hottech(合科泰)"))
      (libsource (lib "easyedapro") (part "1N5819WS"))
    )
    (comp (ref "D269")
      (value "1N5819WS")
      (footprint "easyedapro:SOD-323_L1.8-W1.3-LS2.5-RD")
      (description "Forward Voltage (Vf@If):600mV@1A Reverse Voltage (Vr):40V Average Rectified Current (Io):1A")
      (fields (field (name "Manufacturer") "Hottech(合科泰)"))
      (libsource (lib "easyedapro") (part "1N5819WS"))
    )
    (comp (ref "D270")
      (value "1N5819WS")
      (footprint "easyedapro:SOD-323_L1.8-W1.3-LS2.5-RD")
      (description "Forward Voltage (Vf@If):600mV@1A Reverse Voltage (Vr):40V Average Rectified Current (Io):1A")
      (fields (field (name "Manufacturer") "Hottech(合科泰)"))
      (libsource (lib "easyedapro") (part "1N5819WS"))
    )
    (comp (ref "D271")
      (value "1N5819WS")
      (footprint "easyedapro:SOD-323_L1.8-W1.3-LS2.5-RD")
      (description "Forward Voltage (Vf@If):600mV@1A Reverse Voltage (Vr):40V Average Rectified Current (Io):1A")
      (fields (field (name "Manufacturer") "Hottech(合科泰)"))
      (libsource (lib "easyedapro") (part "1N5819WS"))
    )
    (comp (ref "D272")
      (value "1N5819WS")
      (footprint "easyedapro:SOD-323_L1.8-W1.3-LS2.5-RD")
      (description "Forward Voltage (Vf@If):600mV@1A Reverse Voltage (Vr):40V Average Rectified Current (Io):1A")
      (fields (field (name "Manufacturer") "Hottech(合科泰)"))
      (libsource (lib "easyedapro") (part "1N5819WS"))
    )
    (comp (ref "D273")
      (value "1N5819WS")
      (footprint "easyedapro:SOD-323_L1.8-W1.3-LS2.5-RD")
      (description "Forward Voltage (Vf@If):600mV@1A Reverse Voltage (Vr):40V Average Rectified Current (Io):1A")
      (fields (field (name "Manufacturer") "Hottech(合科泰)"))
      (libsource (lib "easyedapro") (part "1N5819WS"))
    )
    (comp (ref "D274")
      (value "1N5819WS")
      (footprint "easyedapro:SOD-323_L1.8-W1.3-LS2.5-RD")
      (description "Forward Voltage (Vf@If):600mV@1A Reverse Voltage (Vr):40V Average Rectified Current (Io):1A")
      (fields (field (name "Manufacturer") "Hottech(合科泰)"))
      (libsource (lib "easyedapro") (part "1N5819WS"))
    )
    (comp (ref "D275")
      (value "1N5819WS")
      (footprint "easyedapro:SOD-323_L1.8-W1.3-LS2.5-RD")
      (description "Forward Voltage (Vf@If):600mV@1A Reverse Voltage (Vr):40V Average Rectified Current (Io):1A")
      (fields (field (name "Manufacturer") "Hottech(合科泰)"))
      (libsource (lib "easyedapro") (part "1N5819WS"))
    )
    (comp (ref "D276")
      (value "1N5819WS")
      (footprint "easyedapro:SOD-323_L1.8-W1.3-LS2.5-RD")
      (description "Forward Voltage (Vf@If):600mV@1A Reverse Voltage (Vr):40V Average Rectified Current (Io):1A")
      (fields (field (name "Manufacturer") "Hottech(合科泰)"))
      (libsource (lib "easyedapro") (part "1N5819WS"))
    )
    (comp (ref "D277")
      (value "1N5819WS")
      (footprint "easyedapro:SOD-323_L1.8-W1.3-LS2.5-RD")
      (description "Forward Voltage (Vf@If):600mV@1A Reverse Voltage (Vr):40V Average Rectified Current (Io):1A")
      (fields (field (name "Manufacturer") "Hottech(合科泰)"))
      (libsource (lib "easyedapro") (part "1N5819WS"))
    )
    (comp (ref "D278")
      (value "1N5819WS")
      (footprint "easyedapro:SOD-323_L1.8-W1.3-LS2.5-RD")
      (description "Forward Voltage (Vf@If):600mV@1A Reverse Voltage (Vr):40V Average Rectified Current (Io):1A")
      (fields (field (name "Manufacturer") "Hottech(合科泰)"))
      (libsource (lib "easyedapro") (part "1N5819WS"))
    )
    (comp (ref "D279")
      (value "1N5819WS")
      (footprint "easyedapro:SOD-323_L1.8-W1.3-LS2.5-RD")
      (description "Forward Voltage (Vf@If):600mV@1A Reverse Voltage (Vr):40V Average Rectified Current (Io):1A")
      (fields (field (name "Manufacturer") "Hottech(合科泰)"))
      (libsource (lib "easyedapro") (part "1N5819WS"))
    )
    (comp (ref "D280")
      (value "1N5819WS")
      (footprint "easyedapro:SOD-323_L1.8-W1.3-LS2.5-RD")
      (description "Forward Voltage (Vf@If):600mV@1A Reverse Voltage (Vr):40V Average Rectified Current (Io):1A")
      (fields (field (name "Manufacturer") "Hottech(合科泰)"))
      (libsource (lib "easyedapro") (part "1N5819WS"))
    )
    (comp (ref "D281")
      (value "1N5819WS")
      (footprint "easyedapro:SOD-323_L1.8-W1.3-LS2.5-RD")
      (description "Forward Voltage (Vf@If):600mV@1A Reverse Voltage (Vr):40V Average Rectified Current (Io):1A")
      (fields (field (name "Manufacturer") "Hottech(合科泰)"))
      (libsource (lib "easyedapro") (part "1N5819WS"))
    )
    (comp (ref "D282")
      (value "1N5819WS")
      (footprint "easyedapro:SOD-323_L1.8-W1.3-LS2.5-RD")
      (description "Forward Voltage (Vf@If):600mV@1A Reverse Voltage (Vr):40V Average Rectified Current (Io):1A")
      (fields (field (name "Manufacturer") "Hottech(合科泰)"))
      (libsource (lib "easyedapro") (part "1N5819WS"))
    )
    (comp (ref "D283")
      (value "1N5819WS")
      (footprint "easyedapro:SOD-323_L1.8-W1.3-LS2.5-RD")
      (description "Forward Voltage (Vf@If):600mV@1A Reverse Voltage (Vr):40V Average Rectified Current (Io):1A")
      (fields (field (name "Manufacturer") "Hottech(合科泰)"))
      (libsource (lib "easyedapro") (part "1N5819WS"))
    )
    (comp (ref "D284")
      (value "1N5819WS")
      (footprint "easyedapro:SOD-323_L1.8-W1.3-LS2.5-RD")
      (description "Forward Voltage (Vf@If):600mV@1A Reverse Voltage (Vr):40V Average Rectified Current (Io):1A")
      (fields (field (name "Manufacturer") "Hottech(合科泰)"))
      (libsource (lib "easyedapro") (part "1N5819WS"))
    )
    (comp (ref "D285")
      (value "1N5819WS")
      (footprint "easyedapro:SOD-323_L1.8-W1.3-LS2.5-RD")
      (description "Forward Voltage (Vf@If):600mV@1A Reverse Voltage (Vr):40V Average Rectified Current (Io):1A")
      (fields (field (name "Manufacturer") "Hottech(合科泰)"))
      (libsource (lib "easyedapro") (part "1N5819WS"))
    )
    (comp (ref "D286")
      (value "1N5819WS")
      (footprint "easyedapro:SOD-323_L1.8-W1.3-LS2.5-RD")
      (description "Forward Voltage (Vf@If):600mV@1A Reverse Voltage (Vr):40V Average Rectified Current (Io):1A")
      (fields (field (name "Manufacturer") "Hottech(合科泰)"))
      (libsource (lib "easyedapro") (part "1N5819WS"))
    )
    (comp (ref "D287")
      (value "1N5819WS")
      (footprint "easyedapro:SOD-323_L1.8-W1.3-LS2.5-RD")
      (description "Forward Voltage (Vf@If):600mV@1A Reverse Voltage (Vr):40V Average Rectified Current (Io):1A")
      (fields (field (name "Manufacturer") "Hottech(合科泰)"))
      (libsource (lib "easyedapro") (part "1N5819WS"))
    )
    (comp (ref "D288")
      (value "1N5819WS")
      (footprint "easyedapro:SOD-323_L1.8-W1.3-LS2.5-RD")
      (description "Forward Voltage (Vf@If):600mV@1A Reverse Voltage (Vr):40V Average Rectified Current (Io):1A")
      (fields (field (name "Manufacturer") "Hottech(合科泰)"))
      (libsource (lib "easyedapro") (part "1N5819WS"))
    )
    (comp (ref "D289")
      (value "1N5819WS")
      (footprint "easyedapro:SOD-323_L1.8-W1.3-LS2.5-RD")
      (description "Forward Voltage (Vf@If):600mV@1A Reverse Voltage (Vr):40V Average Rectified Current (Io):1A")
      (fields (field (name "Manufacturer") "Hottech(合科泰)"))
      (libsource (lib "easyedapro") (part "1N5819WS"))
    )
    (comp (ref "D290")
      (value "1N5819WS")
      (footprint "easyedapro:SOD-323_L1.8-W1.3-LS2.5-RD")
      (description "Forward Voltage (Vf@If):600mV@1A Reverse Voltage (Vr):40V Average Rectified Current (Io):1A")
      (fields (field (name "Manufacturer") "Hottech(合科泰)"))
      (libsource (lib "easyedapro") (part "1N5819WS"))
    )
    (comp (ref "ENC201")
      (value "PEC12R-4120F-S0012")
      (footprint "easyedapro:SW-TH_PEC12R-4120F-S0012_1")
      (fields (field (name "Manufacturer") "BOURNS"))
      (libsource (lib "easyedapro") (part "PEC12R-4120F-S0012_RF_v1.0"))
    )
    (comp (ref "FPC1")
      (value "FH28-10S-0.5SH(05)")
      (footprint "easyedapro:FFC-SMD_10P-P0.50_FH28-10S-0.5SH-05")
      (fields (field (name "Manufacturer") "HRS(广濑)"))
      (libsource (lib "easyedapro") (part "FH28-10S-0.5SH(05)"))
    )
    (comp (ref "J201")
      (value "CPG151101S11-16")
      (footprint "easyedapro:SMD_KEYBOARD-SW_1")
      (fields (field (name "Manufacturer") "Kailh(凯华)"))
      (libsource (lib "easyedapro") (part "CPG151101S11-16_RF_v1.0"))
    )
    (comp (ref "J202")
      (value "CPG151101S11-16")
      (footprint "easyedapro:SMD_KEYBOARD-SW_1")
      (fields (field (name "Manufacturer") "Kailh(凯华)"))
      (libsource (lib "easyedapro") (part "CPG151101S11-16_RF_v1.0"))
    )
    (comp (ref "J203")
      (value "CPG151101S11-16")
      (footprint "easyedapro:SMD_KEYBOARD-SW_1")
      (fields (field (name "Manufacturer") "Kailh(凯华)"))
      (libsource (lib "easyedapro") (part "CPG151101S11-16_RF_v1.0"))
    )
    (comp (ref "J204")
      (value "CPG151101S11-16")
      (footprint "easyedapro:SMD_KEYBOARD-SW_1")
      (fields (field (name "Manufacturer") "Kailh(凯华)"))
      (libsource (lib "easyedapro") (part "CPG151101S11-16_RF_v1.0"))
    )
    (comp (ref "J205")
      (value "CPG151101S11-16")
      (footprint "easyedapro:SMD_KEYBOARD-SW_1")
      (fields (field (name "Manufacturer") "Kailh(凯华)"))
      (libsource (lib "easyedapro") (part "CPG151101S11-16_RF_v1.0"))
    )
    (comp (ref "J206")
      (value "CPG151101S11-16")
      (footprint "easyedapro:SMD_KEYBOARD-SW_1")
      (fields (field (name "Manufacturer") "Kailh(凯华)"))
      (libsource (lib "easyedapro") (part "CPG151101S11-16_RF_v1.0"))
    )
    (comp (ref "J207")
      (value "CPG151101S11-16")
      (footprint "easyedapro:SMD_KEYBOARD-SW_1")
      (fields (field (name "Manufacturer") "Kailh(凯华)"))
      (libsource (lib "easyedapro") (part "CPG151101S11-16_RF_v1.0"))
    )
    (comp (ref "J208")
      (value "CPG151101S11-16")
      (footprint "easyedapro:SMD_KEYBOARD-SW_1")
      (fields (field (name "Manufacturer") "Kailh(凯华)"))
      (libsource (lib "easyedapro") (part "CPG151101S11-16_RF_v1.0"))
    )
    (comp (ref "J209")
      (value "CPG151101S11-16")
      (footprint "easyedapro:SMD_KEYBOARD-SW_1")
      (fields (field (name "Manufacturer") "Kailh(凯华)"))
      (libsource (lib "easyedapro") (part "CPG151101S11-16_RF_v1.0"))
    )
    (comp (ref "J210")
      (value "CPG151101S11-16")
      (footprint "easyedapro:SMD_KEYBOARD-SW_1")
      (fields (field (name "Manufacturer") "Kailh(凯华)"))
      (libsource (lib "easyedapro") (part "CPG151101S11-16_RF_v1.0"))
    )
    (comp (ref "J211")
      (value "CPG151101S11-16")
      (footprint "easyedapro:SMD_KEYBOARD-SW_1")
      (fields (field (name "Manufacturer") "Kailh(凯华)"))
      (libsource (lib "easyedapro") (part "CPG151101S11-16_RF_v1.0"))
    )
    (comp (ref "J212")
      (value "CPG151101S11-16")
      (footprint "easyedapro:SMD_KEYBOARD-SW_1")
      (fields (field (name "Manufacturer") "Kailh(凯华)"))
      (libsource (lib "easyedapro") (part "CPG151101S11-16_RF_v1.0"))
    )
    (comp (ref "J213")
      (value "CPG151101S11-16")
      (footprint "easyedapro:SMD_KEYBOARD-SW_1")
      (fields (field (name "Manufacturer") "Kailh(凯华)"))
      (libsource (lib "easyedapro") (part "CPG151101S11-16_RF_v1.0"))
    )
    (comp (ref "J214")
      (value "CPG151101S11-16")
      (footprint "easyedapro:SMD_KEYBOARD-SW_1")
      (fields (field (name "Manufacturer") "Kailh(凯华)"))
      (libsource (lib "easyedapro") (part "CPG151101S11-16_RF_v1.0"))
    )
    (comp (ref "J215")
      (value "CPG151101S11-16")
      (footprint "easyedapro:SMD_KEYBOARD-SW_1")
      (fields (field (name "Manufacturer") "Kailh(凯华)"))
      (libsource (lib "easyedapro") (part "CPG151101S11-16_RF_v1.0"))
    )
    (comp (ref "J216")
      (value "CPG151101S11-16")
      (footprint "easyedapro:SMD_KEYBOARD-SW_1")
      (fields (field (name "Manufacturer") "Kailh(凯华)"))
      (libsource (lib "easyedapro") (part "CPG151101S11-16_RF_v1.0"))
    )
    (comp (ref "J217")
      (value "CPG151101S11-16")
      (footprint "easyedapro:SMD_KEYBOARD-SW_1")
      (fields (field (name "Manufacturer") "Kailh(凯华)"))
      (libsource (lib "easyedapro") (part "CPG151101S11-16_RF_v1.0"))
    )
    (comp (ref "J218")
      (value "CPG151101S11-16")
      (footprint "easyedapro:SMD_KEYBOARD-SW_1")
      (fields (field (name "Manufacturer") "Kailh(凯华)"))
      (libsource (lib "easyedapro") (part "CPG151101S11-16_RF_v1.0"))
    )
    (comp (ref "J219")
      (value "CPG151101S11-16")
      (footprint "easyedapro:SMD_KEYBOARD-SW_1")
      (fields (field (name "Manufacturer") "Kailh(凯华)"))
      (libsource (lib "easyedapro") (part "CPG151101S11-16_RF_v1.0"))
    )
    (comp (ref "J220")
      (value "CPG151101S11-16")
      (footprint "easyedapro:SMD_KEYBOARD-SW_1")
      (fields (field (name "Manufacturer") "Kailh(凯华)"))
      (libsource (lib "easyedapro") (part "CPG151101S11-16_RF_v1.0"))
    )
    (comp (ref "J221")
      (value "CPG151101S11-16")
      (footprint "easyedapro:SMD_KEYBOARD-SW_1")
      (fields (field (name "Manufacturer") "Kailh(凯华)"))
      (libsource (lib "easyedapro") (part "CPG151101S11-16_RF_v1.0"))
    )
    (comp (ref "J222")
      (value "CPG151101S11-16")
      (footprint "easyedapro:SMD_KEYBOARD-SW_1")
      (fields (field (name "Manufacturer") "Kailh(凯华)"))
      (libsource (lib "easyedapro") (part "CPG151101S11-16_RF_v1.0"))
    )
    (comp (ref "J223")
      (value "CPG151101S11-16")
      (footprint "easyedapro:SMD_KEYBOARD-SW_1")
      (fields (field (name "Manufacturer") "Kailh(凯华)"))
      (libsource (lib "easyedapro") (part "CPG151101S11-16_RF_v1.0"))
    )
    (comp (ref "J224")
      (value "CPG151101S11-16")
      (footprint "easyedapro:SMD_KEYBOARD-SW_1")
      (fields (field (name "Manufacturer") "Kailh(凯华)"))
      (libsource (lib "easyedapro") (part "CPG151101S11-16_RF_v1.0"))
    )
    (comp (ref "J225")
      (value "CPG151101S11-16")
      (footprint "easyedapro:SMD_KEYBOARD-SW_1")
      (fields (field (name "Manufacturer") "Kailh(凯华)"))
      (libsource (lib "easyedapro") (part "CPG151101S11-16_RF_v1.0"))
    )
    (comp (ref "J226")
      (value "CPG151101S11-16")
      (footprint "easyedapro:SMD_KEYBOARD-SW_1")
      (fields (field (name "Manufacturer") "Kailh(凯华)"))
      (libsource (lib "easyedapro") (part "CPG151101S11-16_RF_v1.0"))
    )
    (comp (ref "J227")
      (value "CPG151101S11-16")
      (footprint "easyedapro:SMD_KEYBOARD-SW_1")
      (fields (field (name "Manufacturer") "Kailh(凯华)"))
      (libsource (lib "easyedapro") (part "CPG151101S11-16_RF_v1.0"))
    )
    (comp (ref "J228")
      (value "CPG151101S11-16")
      (footprint "easyedapro:SMD_KEYBOARD-SW_1")
      (fields (field (name "Manufacturer") "Kailh(凯华)"))
      (libsource (lib "easyedapro") (part "CPG151101S11-16_RF_v1.0"))
    )
    (comp (ref "J229")
      (value "CPG151101S11-16")
      (footprint "easyedapro:SMD_KEYBOARD-SW_1")
      (fields (field (name "Manufacturer") "Kailh(凯华)"))
      (libsource (lib "easyedapro") (part "CPG151101S11-16_RF_v1.0"))
    )
    (comp (ref "J230")
      (value "CPG151101S11-16")
      (footprint "easyedapro:SMD_KEYBOARD-SW_1")
      (fields (field (name "Manufacturer") "Kailh(凯华)"))
      (libsource (lib "easyedapro") (part "CPG151101S11-16_RF_v1.0"))
    )
    (comp (ref "J231")
      (value "CPG151101S11-16")
      (footprint "easyedapro:SMD_KEYBOARD-SW_1")
      (fields (field (name "Manufacturer") "Kailh(凯华)"))
      (libsource (lib "easyedapro") (part "CPG151101S11-16_RF_v1.0"))
    )
    (comp (ref "J232")
      (value "CPG151101S11-16")
      (footprint "easyedapro:SMD_KEYBOARD-SW_1")
      (fields (field (name "Manufacturer") "Kailh(凯华)"))
      (libsource (lib "easyedapro") (part "CPG151101S11-16_RF_v1.0"))
    )
    (comp (ref "J233")
      (value "CPG151101S11-16")
      (footprint "easyedapro:SMD_KEYBOARD-SW_1")
      (fields (field (name "Manufacturer") "Kailh(凯华)"))
      (libsource (lib "easyedapro") (part "CPG151101S11-16_RF_v1.0"))
    )
    (comp (ref "J234")
      (value "CPG151101S11-16")
      (footprint "easyedapro:SMD_KEYBOARD-SW_1")
      (fields (field (name "Manufacturer") "Kailh(凯华)"))
      (libsource (lib "easyedapro") (part "CPG151101S11-16_RF_v1.0"))
    )
    (comp (ref "J235")
      (value "CPG151101S11-16")
      (footprint "easyedapro:SMD_KEYBOARD-SW_1")
      (fields (field (name "Manufacturer") "Kailh(凯华)"))
      (libsource (lib "easyedapro") (part "CPG151101S11-16_RF_v1.0"))
    )
    (comp (ref "J236")
      (value "CPG151101S11-16")
      (footprint "easyedapro:SMD_KEYBOARD-SW_1")
      (fields (field (name "Manufacturer") "Kailh(凯华)"))
      (libsource (lib "easyedapro") (part "CPG151101S11-16_RF_v1.0"))
    )
    (comp (ref "J237")
      (value "CPG151101S11-16")
      (footprint "easyedapro:SMD_KEYBOARD-SW_1")
      (fields (field (name "Manufacturer") "Kailh(凯华)"))
      (libsource (lib "easyedapro") (part "CPG151101S11-16_RF_v1.0"))
    )
    (comp (ref "J238")
      (value "CPG151101S11-16")
      (footprint "easyedapro:SMD_KEYBOARD-SW_1")
      (fields (field (name "Manufacturer") "Kailh(凯华)"))
      (libsource (lib "easyedapro") (part "CPG151101S11-16_RF_v1.0"))
    )
    (comp (ref "J239")
      (value "CPG151101S11-16")
      (footprint "easyedapro:SMD_KEYBOARD-SW_1")
      (fields (field (name "Manufacturer") "Kailh(凯华)"))
      (libsource (lib "easyedapro") (part "CPG151101S11-16_RF_v1.0"))
    )
    (comp (ref "J240")
      (value "CPG151101S11-16")
      (footprint "easyedapro:SMD_KEYBOARD-SW_1")
      (fields (field (name "Manufacturer") "Kailh(凯华)"))
      (libsource (lib "easyedapro") (part "CPG151101S11-16_RF_v1.0"))
    )
    (comp (ref "J241")
      (value "CPG151101S11-16")
      (footprint "easyedapro:SMD_KEYBOARD-SW_1")
      (fields (field (name "Manufacturer") "Kailh(凯华)"))
      (libsource (lib "easyedapro") (part "CPG151101S11-16_RF_v1.0"))
    )
    (comp (ref "J242")
      (value "CPG151101S11-16")
      (footprint "easyedapro:SMD_KEYBOARD-SW_1")
      (fields (field (name "Manufacturer") "Kailh(凯华)"))
      (libsource (lib "easyedapro") (part "CPG151101S11-16_RF_v1.0"))
    )
    (comp (ref "J243")
      (value "CPG151101S11-16")
      (footprint "easyedapro:SMD_KEYBOARD-SW_1")
      (fields (field (name "Manufacturer") "Kailh(凯华)"))
      (libsource (lib "easyedapro") (part "CPG151101S11-16_RF_v1.0"))
    )
    (comp (ref "J244")
      (value "CPG151101S11-16")
      (footprint "easyedapro:SMD_KEYBOARD-SW_1")
      (fields (field (name "Manufacturer") "Kailh(凯华)"))
      (libsource (lib "easyedapro") (part "CPG151101S11-16_RF_v1.0"))
    )
    (comp (ref "J245")
      (value "CPG151101S11-16")
      (footprint "easyedapro:SMD_KEYBOARD-SW_1")
      (fields (field (name "Manufacturer") "Kailh(凯华)"))
      (libsource (lib "easyedapro") (part "CPG151101S11-16_RF_v1.0"))
    )
    (comp (ref "J246")
      (value "CPG151101S11-16")
      (footprint "easyedapro:SMD_KEYBOARD-SW_1")
      (fields (field (name "Manufacturer") "Kailh(凯华)"))
      (libsource (lib "easyedapro") (part "CPG151101S11-16_RF_v1.0"))
    )
    (comp (ref "J247")
      (value "CPG151101S11-16")
      (footprint "easyedapro:SMD_KEYBOARD-SW_1")
      (fields (field (name "Manufacturer") "Kailh(凯华)"))
      (libsource (lib "easyedapro") (part "CPG151101S11-16_RF_v1.0"))
    )
    (comp (ref "J248")
      (value "CPG151101S11-16")
      (footprint "easyedapro:SMD_KEYBOARD-SW_1")
      (fields (field (name "Manufacturer") "Kailh(凯华)"))
      (libsource (lib "easyedapro") (part "CPG151101S11-16_RF_v1.0"))
    )
    (comp (ref "J249")
      (value "CPG151101S11-16")
      (footprint "easyedapro:SMD_KEYBOARD-SW_1")
      (fields (field (name "Manufacturer") "Kailh(凯华)"))
      (libsource (lib "easyedapro") (part "CPG151101S11-16_RF_v1.0"))
    )
    (comp (ref "J250")
      (value "CPG151101S11-16")
      (footprint "easyedapro:SMD_KEYBOARD-SW_1")
      (fields (field (name "Manufacturer") "Kailh(凯华)"))
      (libsource (lib "easyedapro") (part "CPG151101S11-16_RF_v1.0"))
    )
    (comp (ref "J251")
      (value "CPG151101S11-16")
      (footprint "easyedapro:SMD_KEYBOARD-SW_1")
      (fields (field (name "Manufacturer") "Kailh(凯华)"))
      (libsource (lib "easyedapro") (part "CPG151101S11-16_RF_v1.0"))
    )
    (comp (ref "J252")
      (value "CPG151101S11-16")
      (footprint "easyedapro:SMD_KEYBOARD-SW_1")
      (fields (field (name "Manufacturer") "Kailh(凯华)"))
      (libsource (lib "easyedapro") (part "CPG151101S11-16_RF_v1.0"))
    )
    (comp (ref "J253")
      (value "CPG151101S11-16")
      (footprint "easyedapro:SMD_KEYBOARD-SW_1")
      (fields (field (name "Manufacturer") "Kailh(凯华)"))
      (libsource (lib "easyedapro") (part "CPG151101S11-16_RF_v1.0"))
    )
    (comp (ref "J254")
      (value "CPG151101S11-16")
      (footprint "easyedapro:SMD_KEYBOARD-SW_1")
      (fields (field (name "Manufacturer") "Kailh(凯华)"))
      (libsource (lib "easyedapro") (part "CPG151101S11-16_RF_v1.0"))
    )
    (comp (ref "J255")
      (value "CPG151101S11-16")
      (footprint "easyedapro:SMD_KEYBOARD-SW_1")
      (fields (field (name "Manufacturer") "Kailh(凯华)"))
      (libsource (lib "easyedapro") (part "CPG151101S11-16_RF_v1.0"))
    )
    (comp (ref "J256")
      (value "CPG151101S11-16")
      (footprint "easyedapro:SMD_KEYBOARD-SW_1")
      (fields (field (name "Manufacturer") "Kailh(凯华)"))
      (libsource (lib "easyedapro") (part "CPG151101S11-16_RF_v1.0"))
    )
    (comp (ref "J257")
      (value "CPG151101S11-16")
      (footprint "easyedapro:SMD_KEYBOARD-SW_1")
      (fields (field (name "Manufacturer") "Kailh(凯华)"))
      (libsource (lib "easyedapro") (part "CPG151101S11-16_RF_v1.0"))
    )
    (comp (ref "J258")
      (value "CPG151101S11-16")
      (footprint "easyedapro:SMD_KEYBOARD-SW_1")
      (fields (field (name "Manufacturer") "Kailh(凯华)"))
      (libsource (lib "easyedapro") (part "CPG151101S11-16_RF_v1.0"))
    )
    (comp (ref "J259")
      (value "CPG151101S11-16")
      (footprint "easyedapro:SMD_KEYBOARD-SW_1")
      (fields (field (name "Manufacturer") "Kailh(凯华)"))
      (libsource (lib "easyedapro") (part "CPG151101S11-16_RF_v1.0"))
    )
    (comp (ref "J260")
      (value "CPG151101S11-16")
      (footprint "easyedapro:SMD_KEYBOARD-SW_1")
      (fields (field (name "Manufacturer") "Kailh(凯华)"))
      (libsource (lib "easyedapro") (part "CPG151101S11-16_RF_v1.0"))
    )
    (comp (ref "J261")
      (value "CPG151101S11-16")
      (footprint "easyedapro:SMD_KEYBOARD-SW_1")
      (fields (field (name "Manufacturer") "Kailh(凯华)"))
      (libsource (lib "easyedapro") (part "CPG151101S11-16_RF_v1.0"))
    )
    (comp (ref "J262")
      (value "CPG151101S11-16")
      (footprint "easyedapro:SMD_KEYBOARD-SW_1")
      (fields (field (name "Manufacturer") "Kailh(凯华)"))
      (libsource (lib "easyedapro") (part "CPG151101S11-16_RF_v1.0"))
    )
    (comp (ref "J263")
      (value "CPG151101S11-16")
      (footprint "easyedapro:SMD_KEYBOARD-SW_1")
      (fields (field (name "Manufacturer") "Kailh(凯华)"))
      (libsource (lib "easyedapro") (part "CPG151101S11-16_RF_v1.0"))
    )
    (comp (ref "J264")
      (value "CPG151101S11-16")
      (footprint "easyedapro:SMD_KEYBOARD-SW_1")
      (fields (field (name "Manufacturer") "Kailh(凯华)"))
      (libsource (lib "easyedapro") (part "CPG151101S11-16_RF_v1.0"))
    )
    (comp (ref "J265")
      (value "CPG151101S11-16")
      (footprint "easyedapro:SMD_KEYBOARD-SW_1")
      (fields (field (name "Manufacturer") "Kailh(凯华)"))
      (libsource (lib "easyedapro") (part "CPG151101S11-16_RF_v1.0"))
    )
    (comp (ref "J266")
      (value "CPG151101S11-16")
      (footprint "easyedapro:SMD_KEYBOARD-SW_1")
      (fields (field (name "Manufacturer") "Kailh(凯华)"))
      (libsource (lib "easyedapro") (part "CPG151101S11-16_RF_v1.0"))
    )
    (comp (ref "J267")
      (value "CPG151101S11-16")
      (footprint "easyedapro:SMD_KEYBOARD-SW_1")
      (fields (field (name "Manufacturer") "Kailh(凯华)"))
      (libsource (lib "easyedapro") (part "CPG151101S11-16_RF_v1.0"))
    )
    (comp (ref "J268")
      (value "CPG151101S11-16")
      (footprint "easyedapro:SMD_KEYBOARD-SW_1")
      (fields (field (name "Manufacturer") "Kailh(凯华)"))
      (libsource (lib "easyedapro") (part "CPG151101S11-16_RF_v1.0"))
    )
    (comp (ref "J269")
      (value "CPG151101S11-16")
      (footprint "easyedapro:SMD_KEYBOARD-SW_1")
      (fields (field (name "Manufacturer") "Kailh(凯华)"))
      (libsource (lib "easyedapro") (part "CPG151101S11-16_RF_v1.0"))
    )
    (comp (ref "J270")
      (value "CPG151101S11-16")
      (footprint "easyedapro:SMD_KEYBOARD-SW_1")
      (fields (field (name "Manufacturer") "Kailh(凯华)"))
      (libsource (lib "easyedapro") (part "CPG151101S11-16_RF_v1.0"))
    )
    (comp (ref "J271")
      (value "CPG151101S11-16")
      (footprint "easyedapro:SMD_KEYBOARD-SW_1")
      (fields (field (name "Manufacturer") "Kailh(凯华)"))
      (libsource (lib "easyedapro") (part "CPG151101S11-16_RF_v1.0"))
    )
    (comp (ref "J272")
      (value "CPG151101S11-16")
      (footprint "easyedapro:SMD_KEYBOARD-SW_1")
      (fields (field (name "Manufacturer") "Kailh(凯华)"))
      (libsource (lib "easyedapro") (part "CPG151101S11-16_RF_v1.0"))
    )
    (comp (ref "J273")
      (value "CPG151101S11-16")
      (footprint "easyedapro:SMD_KEYBOARD-SW_1")
      (fields (field (name "Manufacturer") "Kailh(凯华)"))
      (libsource (lib "easyedapro") (part "CPG151101S11-16_RF_v1.0"))
    )
    (comp (ref "J274")
      (value "CPG151101S11-16")
      (footprint "easyedapro:SMD_KEYBOARD-SW_1")
      (fields (field (name "Manufacturer") "Kailh(凯华)"))
      (libsource (lib "easyedapro") (part "CPG151101S11-16_RF_v1.0"))
    )
    (comp (ref "J275")
      (value "CPG151101S11-16")
      (footprint "easyedapro:SMD_KEYBOARD-SW_1")
      (fields (field (name "Manufacturer") "Kailh(凯华)"))
      (libsource (lib "easyedapro") (part "CPG151101S11-16_RF_v1.0"))
    )
    (comp (ref "J276")
      (value "CPG151101S11-16")
      (footprint "easyedapro:SMD_KEYBOARD-SW_1")
      (fields (field (name "Manufacturer") "Kailh(凯华)"))
      (libsource (lib "easyedapro") (part "CPG151101S11-16_RF_v1.0"))
    )
    (comp (ref "J277")
      (value "CPG151101S11-16")
      (footprint "easyedapro:SMD_KEYBOARD-SW_1")
      (fields (field (name "Manufacturer") "Kailh(凯华)"))
      (libsource (lib "easyedapro") (part "CPG151101S11-16_RF_v1.0"))
    )
    (comp (ref "J278")
      (value "CPG151101S11-16")
      (footprint "easyedapro:SMD_KEYBOARD-SW_1")
      (fields (field (name "Manufacturer") "Kailh(凯华)"))
      (libsource (lib "easyedapro") (part "CPG151101S11-16_RF_v1.0"))
    )
    (comp (ref "MH201")
      (value "STANDOFF_M2.5x3.5MM")
      (footprint "easyedapro:STANDOFF_M2.5x3.5MM_RF_v1.0")
      (description "Standoff, Steel, M2.5, Hex Female-Female, 3.5 mm, 4.9 mm, WA-SMSI Series")
      (fields (field (name "Manufacturer") "WURTH ELEKTRONIK"))
      (libsource (lib "easyedapro") (part "9774035151R_RF_v1.0"))
    )
    (comp (ref "MH202")
      (value "STANDOFF_M2.5x3.5MM")
      (footprint "easyedapro:STANDOFF_M2.5x3.5MM_RF_v1.0")
      (description "Standoff, Steel, M2.5, Hex Female-Female, 3.5 mm, 4.9 mm, WA-SMSI Series")
      (fields (field (name "Manufacturer") "WURTH ELEKTRONIK"))
      (libsource (lib "easyedapro") (part "9774035151R_RF_v1.0"))
    )
    (comp (ref "MH203")
      (value "STANDOFF_M2.5x3.5MM")
      (footprint "easyedapro:STANDOFF_M2.5x3.5MM_RF_v1.0")
      (description "Standoff, Steel, M2.5, Hex Female-Female, 3.5 mm, 4.9 mm, WA-SMSI Series")
      (fields (field (name "Manufacturer") "WURTH ELEKTRONIK"))
      (libsource (lib "easyedapro") (part "9774035151R_RF_v1.0"))
    )
    (comp (ref "MH204")
      (value "STANDOFF_M2.5x3.5MM")
      (footprint "easyedapro:STANDOFF_M2.5x3.5MM_RF_v1.0")
      (description "Standoff, Steel, M2.5, Hex Female-Female, 3.5 mm, 4.9 mm, WA-SMSI Series")
      (fields (field (name "Manufacturer") "WURTH ELEKTRONIK"))
      (libsource (lib "easyedapro") (part "9774035151R_RF_v1.0"))
    )
    (comp (ref "MH205")
      (value "~")
      (footprint "easyedapro:MH_7.5X3.2MM_RF_v1.0")
      (libsource (lib "easyedapro") (part "MH_7.5X3.2MM_RF_v1.0"))
    )
    (comp (ref "MH206")
      (value "~")
      (footprint "easyedapro:MH_7.5X3.2MM_RF_v1.0")
      (libsource (lib "easyedapro") (part "MH_7.5X3.2MM_RF_v1.0"))
    )
    (comp (ref "MH207")
      (value "~")
      (footprint "easyedapro:MH_7.5X3.2MM_RF_v1.0")
      (libsource (lib "easyedapro") (part "MH_7.5X3.2MM_RF_v1.0"))
    )
    (comp (ref "MH208")
      (value "~")
      (footprint "easyedapro:MH_7.5X3.2MM_RF_v1.0")
      (libsource (lib "easyedapro") (part "MH_7.5X3.2MM_RF_v1.0"))
    )
    (comp (ref "R201")
      (value "10kΩ")
      (footprint "easyedapro:R0402")
      (fields
        (field (name "Manufacturer Part") "0402WGF1002TCE")
        (field (name "Manufacturer") "UNI-ROYAL(厚声)")
      )
      (libsource (lib "easyedapro") (part "0402WGF1002TCE"))
    )
    (comp (ref "R202")
      (value "10kΩ")
      (footprint "easyedapro:R0402")
      (fields
        (field (name "Manufacturer Part") "0402WGF1002TCE")
        (field (name "Manufacturer") "UNI-ROYAL(厚声)")
      )
      (libsource (lib "easyedapro") (part "0402WGF1002TCE"))
    )
    (comp (ref "R205")
      (value "10kΩ")
      (footprint "easyedapro:R0402")
      (fields
        (field (name "Manufacturer Part") "0402WGF1002TCE")
        (field (name "Manufacturer") "UNI-ROYAL(厚声)")
      )
      (libsource (lib "easyedapro") (part "0402WGF1002TCE"))
    )
    (comp (ref "R207")
      (value "10kΩ")
      (footprint "easyedapro:R0402")
      (fields
        (field (name "Manufacturer Part") "0402WGF1002TCE")
        (field (name "Manufacturer") "UNI-ROYAL(厚声)")
      )
      (libsource (lib "easyedapro") (part "0402WGF1002TCE"))
    )
    (comp (ref "R223")
      (value "10kΩ")
      (footprint "easyedapro:R0402")
      (fields
        (field (name "Manufacturer Part") "0402WGF1002TCE")
        (field (name "Manufacturer") "UNI-ROYAL(厚声)")
      )
      (libsource (lib "easyedapro") (part "0402WGF1002TCE"))
    )
    (comp (ref "R224")
      (value "10kΩ")
      (footprint "easyedapro:R0402")
      (fields
        (field (name "Manufacturer Part") "0402WGF1002TCE")
        (field (name "Manufacturer") "UNI-ROYAL(厚声)")
      )
      (libsource (lib "easyedapro") (part "0402WGF1002TCE"))
    )
    (comp (ref "SW201")
      (value "CPG151101S21")
      (footprint "easyedapro:KEY-TH_CPG1511F01S0X_1")
      (fields (field (name "Manufacturer") "Kailh(凯华)"))
      (libsource (lib "easyedapro") (part "CPG151101S21 RF v1.0"))
    )
    (comp (ref "SW202")
      (value "CPG151101S21")
      (footprint "easyedapro:KEY-TH_CPG1511F01S0X_1")
      (fields (field (name "Manufacturer") "Kailh(凯华)"))
      (libsource (lib "easyedapro") (part "CPG151101S21 RF v1.0"))
    )
    (comp (ref "SW203")
      (value "CPG151101S21")
      (footprint "easyedapro:KEY-TH_CPG1511F01S0X_1")
      (fields (field (name "Manufacturer") "Kailh(凯华)"))
      (libsource (lib "easyedapro") (part "CPG151101S21 RF v1.0"))
    )
    (comp (ref "SW204")
      (value "CPG151101S21")
      (footprint "easyedapro:KEY-TH_CPG1511F01S0X_1")
      (fields (field (name "Manufacturer") "Kailh(凯华)"))
      (libsource (lib "easyedapro") (part "CPG151101S21 RF v1.0"))
    )
    (comp (ref "SW205")
      (value "CPG151101S21")
      (footprint "easyedapro:KEY-TH_CPG1511F01S0X_1")
      (fields (field (name "Manufacturer") "Kailh(凯华)"))
      (libsource (lib "easyedapro") (part "CPG151101S21 RF v1.0"))
    )
    (comp (ref "SW206")
      (value "CPG151101S21")
      (footprint "easyedapro:KEY-TH_CPG1511F01S0X_1")
      (fields (field (name "Manufacturer") "Kailh(凯华)"))
      (libsource (lib "easyedapro") (part "CPG151101S21 RF v1.0"))
    )
    (comp (ref "SW207")
      (value "CPG151101S21")
      (footprint "easyedapro:KEY-TH_CPG1511F01S0X_1")
      (fields (field (name "Manufacturer") "Kailh(凯华)"))
      (libsource (lib "easyedapro") (part "CPG151101S21 RF v1.0"))
    )
    (comp (ref "SW208")
      (value "CPG151101S21")
      (footprint "easyedapro:KEY-TH_CPG1511F01S0X_1")
      (fields (field (name "Manufacturer") "Kailh(凯华)"))
      (libsource (lib "easyedapro") (part "CPG151101S21 RF v1.0"))
    )
    (comp (ref "SW209")
      (value "CPG151101S21")
      (footprint "easyedapro:KEY-TH_CPG1511F01S0X_1")
      (fields (field (name "Manufacturer") "Kailh(凯华)"))
      (libsource (lib "easyedapro") (part "CPG151101S21 RF v1.0"))
    )
    (comp (ref "SW210")
      (value "CPG151101S21")
      (footprint "easyedapro:KEY-TH_CPG1511F01S0X_1")
      (fields (field (name "Manufacturer") "Kailh(凯华)"))
      (libsource (lib "easyedapro") (part "CPG151101S21 RF v1.0"))
    )
    (comp (ref "SW211")
      (value "CPG151101S21")
      (footprint "easyedapro:KEY-TH_CPG1511F01S0X_1")
      (fields (field (name "Manufacturer") "Kailh(凯华)"))
      (libsource (lib "easyedapro") (part "CPG151101S21 RF v1.0"))
    )
    (comp (ref "SW212")
      (value "CPG151101S21")
      (footprint "easyedapro:KEY-TH_CPG1511F01S0X_1")
      (fields (field (name "Manufacturer") "Kailh(凯华)"))
      (libsource (lib "easyedapro") (part "CPG151101S21 RF v1.0"))
    )
    (comp (ref "SW213")
      (value "CPG151101S21")
      (footprint "easyedapro:KEY-TH_CPG1511F01S0X_1")
      (fields (field (name "Manufacturer") "Kailh(凯华)"))
      (libsource (lib "easyedapro") (part "CPG151101S21 RF v1.0"))
    )
    (comp (ref "SW214")
      (value "CPG151101S21")
      (footprint "easyedapro:KEY-TH_CPG1511F01S0X_1")
      (fields (field (name "Manufacturer") "Kailh(凯华)"))
      (libsource (lib "easyedapro") (part "CPG151101S21 RF v1.0"))
    )
    (comp (ref "SW215")
      (value "CPG151101S21")
      (footprint "easyedapro:KEY-TH_CPG1511F01S0X_1")
      (fields (field (name "Manufacturer") "Kailh(凯华)"))
      (libsource (lib "easyedapro") (part "CPG151101S21 RF v1.0"))
    )
    (comp (ref "SW216")
      (value "CPG151101S21")
      (footprint "easyedapro:KEY-TH_CPG1511F01S0X_1")
      (fields (field (name "Manufacturer") "Kailh(凯华)"))
      (libsource (lib "easyedapro") (part "CPG151101S21 RF v1.0"))
    )
    (comp (ref "SW217")
      (value "CPG151101S21")
      (footprint "easyedapro:KEY-TH_CPG1511F01S0X_1")
      (fields (field (name "Manufacturer") "Kailh(凯华)"))
      (libsource (lib "easyedapro") (part "CPG151101S21 RF v1.0"))
    )
    (comp (ref "SW218")
      (value "CPG151101S21")
      (footprint "easyedapro:KEY-TH_CPG1511F01S0X_1")
      (fields (field (name "Manufacturer") "Kailh(凯华)"))
      (libsource (lib "easyedapro") (part "CPG151101S21 RF v1.0"))
    )
    (comp (ref "SW219")
      (value "CPG151101S21")
      (footprint "easyedapro:KEY-TH_CPG1511F01S0X_1")
      (fields (field (name "Manufacturer") "Kailh(凯华)"))
      (libsource (lib "easyedapro") (part "CPG151101S21 RF v1.0"))
    )
    (comp (ref "SW220")
      (value "CPG151101S21")
      (footprint "easyedapro:KEY-TH_CPG1511F01S0X_1")
      (fields (field (name "Manufacturer") "Kailh(凯华)"))
      (libsource (lib "easyedapro") (part "CPG151101S21 RF v1.0"))
    )
    (comp (ref "SW221")
      (value "CPG151101S21")
      (footprint "easyedapro:KEY-TH_CPG1511F01S0X_1")
      (fields (field (name "Manufacturer") "Kailh(凯华)"))
      (libsource (lib "easyedapro") (part "CPG151101S21 RF v1.0"))
    )
    (comp (ref "SW222")
      (value "CPG151101S21")
      (footprint "easyedapro:KEY-TH_CPG1511F01S0X_1")
      (fields (field (name "Manufacturer") "Kailh(凯华)"))
      (libsource (lib "easyedapro") (part "CPG151101S21 RF v1.0"))
    )
    (comp (ref "SW223")
      (value "CPG151101S21")
      (footprint "easyedapro:KEY-TH_CPG1511F01S0X_1")
      (fields (field (name "Manufacturer") "Kailh(凯华)"))
      (libsource (lib "easyedapro") (part "CPG151101S21 RF v1.0"))
    )
    (comp (ref "SW224")
      (value "CPG151101S21")
      (footprint "easyedapro:KEY-TH_CPG1511F01S0X_1")
      (fields (field (name "Manufacturer") "Kailh(凯华)"))
      (libsource (lib "easyedapro") (part "CPG151101S21 RF v1.0"))
    )
    (comp (ref "SW225")
      (value "CPG151101S21")
      (footprint "easyedapro:KEY-TH_CPG1511F01S0X_1")
      (fields (field (name "Manufacturer") "Kailh(凯华)"))
      (libsource (lib "easyedapro") (part "CPG151101S21 RF v1.0"))
    )
    (comp (ref "SW226")
      (value "CPG151101S21")
      (footprint "easyedapro:KEY-TH_CPG1511F01S0X_1")
      (fields (field (name "Manufacturer") "Kailh(凯华)"))
      (libsource (lib "easyedapro") (part "CPG151101S21 RF v1.0"))
    )
    (comp (ref "SW227")
      (value "CPG151101S21")
      (footprint "easyedapro:KEY-TH_CPG1511F01S0X_1")
      (fields (field (name "Manufacturer") "Kailh(凯华)"))
      (libsource (lib "easyedapro") (part "CPG151101S21 RF v1.0"))
    )
    (comp (ref "SW228")
      (value "CPG151101S21")
      (footprint "easyedapro:KEY-TH_CPG1511F01S0X_1")
      (fields (field (name "Manufacturer") "Kailh(凯华)"))
      (libsource (lib "easyedapro") (part "CPG151101S21 RF v1.0"))
    )
    (comp (ref "SW229")
      (value "CPG151101S21")
      (footprint "easyedapro:KEY-TH_CPG1511F01S0X_1")
      (fields (field (name "Manufacturer") "Kailh(凯华)"))
      (libsource (lib "easyedapro") (part "CPG151101S21 RF v1.0"))
    )
    (comp (ref "SW230")
      (value "CPG151101S21")
      (footprint "easyedapro:KEY-TH_CPG1511F01S0X_1")
      (fields (field (name "Manufacturer") "Kailh(凯华)"))
      (libsource (lib "easyedapro") (part "CPG151101S21 RF v1.0"))
    )
    (comp (ref "SW231")
      (value "CPG151101S21")
      (footprint "easyedapro:KEY-TH_CPG1511F01S0X_1")
      (fields (field (name "Manufacturer") "Kailh(凯华)"))
      (libsource (lib "easyedapro") (part "CPG151101S21 RF v1.0"))
    )
    (comp (ref "SW232")
      (value "CPG151101S21")
      (footprint "easyedapro:KEY-TH_CPG1511F01S0X_1")
      (fields (field (name "Manufacturer") "Kailh(凯华)"))
      (libsource (lib "easyedapro") (part "CPG151101S21 RF v1.0"))
    )
    (comp (ref "SW233")
      (value "CPG151101S21")
      (footprint "easyedapro:KEY-TH_CPG1511F01S0X_1")
      (fields (field (name "Manufacturer") "Kailh(凯华)"))
      (libsource (lib "easyedapro") (part "CPG151101S21 RF v1.0"))
    )
    (comp (ref "SW234")
      (value "CPG151101S21")
      (footprint "easyedapro:KEY-TH_CPG1511F01S0X_1")
      (fields (field (name "Manufacturer") "Kailh(凯华)"))
      (libsource (lib "easyedapro") (part "CPG151101S21 RF v1.0"))
    )
    (comp (ref "SW235")
      (value "CPG151101S21")
      (footprint "easyedapro:KEY-TH_CPG1511F01S0X_1")
      (fields (field (name "Manufacturer") "Kailh(凯华)"))
      (libsource (lib "easyedapro") (part "CPG151101S21 RF v1.0"))
    )
    (comp (ref "SW236")
      (value "CPG151101S21")
      (footprint "easyedapro:KEY-TH_CPG1511F01S0X_1")
      (fields (field (name "Manufacturer") "Kailh(凯华)"))
      (libsource (lib "easyedapro") (part "CPG151101S21 RF v1.0"))
    )
    (comp (ref "SW237")
      (value "CPG151101S21")
      (footprint "easyedapro:KEY-TH_CPG1511F01S0X_1")
      (fields (field (name "Manufacturer") "Kailh(凯华)"))
      (libsource (lib "easyedapro") (part "CPG151101S21 RF v1.0"))
    )
    (comp (ref "SW238")
      (value "CPG151101S21")
      (footprint "easyedapro:KEY-TH_CPG1511F01S0X_1")
      (fields (field (name "Manufacturer") "Kailh(凯华)"))
      (libsource (lib "easyedapro") (part "CPG151101S21 RF v1.0"))
    )
    (comp (ref "SW239")
      (value "CPG151101S21")
      (footprint "easyedapro:KEY-TH_CPG1511F01S0X_1")
      (fields (field (name "Manufacturer") "Kailh(凯华)"))
      (libsource (lib "easyedapro") (part "CPG151101S21 RF v1.0"))
    )
    (comp (ref "SW240")
      (value "CPG151101S21")
      (footprint "easyedapro:KEY-TH_CPG1511F01S0X_1")
      (fields (field (name "Manufacturer") "Kailh(凯华)"))
      (libsource (lib "easyedapro") (part "CPG151101S21 RF v1.0"))
    )
    (comp (ref "SW241")
      (value "CPG151101S21")
      (footprint "easyedapro:KEY-TH_CPG1511F01S0X_1")
      (fields (field (name "Manufacturer") "Kailh(凯华)"))
      (libsource (lib "easyedapro") (part "CPG151101S21 RF v1.0"))
    )
    (comp (ref "SW242")
      (value "CPG151101S21")
      (footprint "easyedapro:KEY-TH_CPG1511F01S0X_1")
      (fields (field (name "Manufacturer") "Kailh(凯华)"))
      (libsource (lib "easyedapro") (part "CPG151101S21 RF v1.0"))
    )
    (comp (ref "SW243")
      (value "CPG151101S21")
      (footprint "easyedapro:KEY-TH_CPG1511F01S0X_1")
      (fields (field (name "Manufacturer") "Kailh(凯华)"))
      (libsource (lib "easyedapro") (part "CPG151101S21 RF v1.0"))
    )
    (comp (ref "SW244")
      (value "CPG151101S21")
      (footprint "easyedapro:KEY-TH_CPG1511F01S0X_1")
      (fields (field (name "Manufacturer") "Kailh(凯华)"))
      (libsource (lib "easyedapro") (part "CPG151101S21 RF v1.0"))
    )
    (comp (ref "SW245")
      (value "CPG151101S21")
      (footprint "easyedapro:KEY-TH_CPG1511F01S0X_1")
      (fields (field (name "Manufacturer") "Kailh(凯华)"))
      (libsource (lib "easyedapro") (part "CPG151101S21 RF v1.0"))
    )
    (comp (ref "SW246")
      (value "CPG151101S21")
      (footprint "easyedapro:KEY-TH_CPG1511F01S0X_1")
      (fields (field (name "Manufacturer") "Kailh(凯华)"))
      (libsource (lib "easyedapro") (part "CPG151101S21 RF v1.0"))
    )
    (comp (ref "SW247")
      (value "CPG151101S21")
      (footprint "easyedapro:KEY-TH_CPG1511F01S0X_1")
      (fields (field (name "Manufacturer") "Kailh(凯华)"))
      (libsource (lib "easyedapro") (part "CPG151101S21 RF v1.0"))
    )
    (comp (ref "SW248")
      (value "CPG151101S21")
      (footprint "easyedapro:KEY-TH_CPG1511F01S0X_1")
      (fields (field (name "Manufacturer") "Kailh(凯华)"))
      (libsource (lib "easyedapro") (part "CPG151101S21 RF v1.0"))
    )
    (comp (ref "SW249")
      (value "CPG151101S21")
      (footprint "easyedapro:KEY-TH_CPG1511F01S0X_1")
      (fields (field (name "Manufacturer") "Kailh(凯华)"))
      (libsource (lib "easyedapro") (part "CPG151101S21 RF v1.0"))
    )
    (comp (ref "SW250")
      (value "CPG151101S21")
      (footprint "easyedapro:KEY-TH_CPG1511F01S0X_1")
      (fields (field (name "Manufacturer") "Kailh(凯华)"))
      (libsource (lib "easyedapro") (part "CPG151101S21 RF v1.0"))
    )
    (comp (ref "SW251")
      (value "CPG151101S21")
      (footprint "easyedapro:KEY-TH_CPG1511F01S0X_1")
      (fields (field (name "Manufacturer") "Kailh(凯华)"))
      (libsource (lib "easyedapro") (part "CPG151101S21 RF v1.0"))
    )
    (comp (ref "SW252")
      (value "CPG151101S21")
      (footprint "easyedapro:KEY-TH_CPG1511F01S0X_1")
      (fields (field (name "Manufacturer") "Kailh(凯华)"))
      (libsource (lib "easyedapro") (part "CPG151101S21 RF v1.0"))
    )
    (comp (ref "SW253")
      (value "CPG151101S21")
      (footprint "easyedapro:KEY-TH_CPG1511F01S0X_1")
      (fields (field (name "Manufacturer") "Kailh(凯华)"))
      (libsource (lib "easyedapro") (part "CPG151101S21 RF v1.0"))
    )
    (comp (ref "SW254")
      (value "CPG151101S21")
      (footprint "easyedapro:KEY-TH_CPG1511F01S0X_1")
      (fields (field (name "Manufacturer") "Kailh(凯华)"))
      (libsource (lib "easyedapro") (part "CPG151101S21 RF v1.0"))
    )
    (comp (ref "SW255")
      (value "CPG151101S21")
      (footprint "easyedapro:KEY-TH_CPG1511F01S0X_1")
      (fields (field (name "Manufacturer") "Kailh(凯华)"))
      (libsource (lib "easyedapro") (part "CPG151101S21 RF v1.0"))
    )
    (comp (ref "SW256")
      (value "CPG151101S21")
      (footprint "easyedapro:KEY-TH_CPG1511F01S0X_1")
      (fields (field (name "Manufacturer") "Kailh(凯华)"))
      (libsource (lib "easyedapro") (part "CPG151101S21 RF v1.0"))
    )
    (comp (ref "SW257")
      (value "CPG151101S21")
      (footprint "easyedapro:KEY-TH_CPG1511F01S0X_1")
      (fields (field (name "Manufacturer") "Kailh(凯华)"))
      (libsource (lib "easyedapro") (part "CPG151101S21 RF v1.0"))
    )
    (comp (ref "SW258")
      (value "CPG151101S21")
      (footprint "easyedapro:KEY-TH_CPG1511F01S0X_1")
      (fields (field (name "Manufacturer") "Kailh(凯华)"))
      (libsource (lib "easyedapro") (part "CPG151101S21 RF v1.0"))
    )
    (comp (ref "SW259")
      (value "CPG151101S21")
      (footprint "easyedapro:KEY-TH_CPG1511F01S0X_1")
      (fields (field (name "Manufacturer") "Kailh(凯华)"))
      (libsource (lib "easyedapro") (part "CPG151101S21 RF v1.0"))
    )
    (comp (ref "SW260")
      (value "CPG151101S21")
      (footprint "easyedapro:KEY-TH_CPG1511F01S0X_1")
      (fields (field (name "Manufacturer") "Kailh(凯华)"))
      (libsource (lib "easyedapro") (part "CPG151101S21 RF v1.0"))
    )
    (comp (ref "SW261")
      (value "CPG151101S21")
      (footprint "easyedapro:KEY-TH_CPG1511F01S0X_1")
      (fields (field (name "Manufacturer") "Kailh(凯华)"))
      (libsource (lib "easyedapro") (part "CPG151101S21 RF v1.0"))
    )
    (comp (ref "SW262")
      (value "CPG151101S21")
      (footprint "easyedapro:KEY-TH_CPG1511F01S0X_1")
      (fields (field (name "Manufacturer") "Kailh(凯华)"))
      (libsource (lib "easyedapro") (part "CPG151101S21 RF v1.0"))
    )
    (comp (ref "SW263")
      (value "CPG151101S21")
      (footprint "easyedapro:KEY-TH_CPG1511F01S0X_1")
      (fields (field (name "Manufacturer") "Kailh(凯华)"))
      (libsource (lib "easyedapro") (part "CPG151101S21 RF v1.0"))
    )
    (comp (ref "SW264")
      (value "CPG151101S21")
      (footprint "easyedapro:KEY-TH_CPG1511F01S0X_1")
      (fields (field (name "Manufacturer") "Kailh(凯华)"))
      (libsource (lib "easyedapro") (part "CPG151101S21 RF v1.0"))
    )
    (comp (ref "SW265")
      (value "CPG151101S21")
      (footprint "easyedapro:KEY-TH_CPG1511F01S0X_1")
      (fields (field (name "Manufacturer") "Kailh(凯华)"))
      (libsource (lib "easyedapro") (part "CPG151101S21 RF v1.0"))
    )
    (comp (ref "SW266")
      (value "CPG151101S21")
      (footprint "easyedapro:KEY-TH_CPG1511F01S0X_1")
      (fields (field (name "Manufacturer") "Kailh(凯华)"))
      (libsource (lib "easyedapro") (part "CPG151101S21 RF v1.0"))
    )
    (comp (ref "SW267")
      (value "CPG151101S21")
      (footprint "easyedapro:KEY-TH_CPG1511F01S0X_1")
      (fields (field (name "Manufacturer") "Kailh(凯华)"))
      (libsource (lib "easyedapro") (part "CPG151101S21 RF v1.0"))
    )
    (comp (ref "SW268")
      (value "CPG151101S21")
      (footprint "easyedapro:KEY-TH_CPG1511F01S0X_1")
      (fields (field (name "Manufacturer") "Kailh(凯华)"))
      (libsource (lib "easyedapro") (part "CPG151101S21 RF v1.0"))
    )
    (comp (ref "SW269")
      (value "CPG151101S21")
      (footprint "easyedapro:KEY-TH_CPG1511F01S0X_1")
      (fields (field (name "Manufacturer") "Kailh(凯华)"))
      (libsource (lib "easyedapro") (part "CPG151101S21 RF v1.0"))
    )
    (comp (ref "SW270")
      (value "CPG151101S21")
      (footprint "easyedapro:KEY-TH_CPG1511F01S0X_1")
      (fields (field (name "Manufacturer") "Kailh(凯华)"))
      (libsource (lib "easyedapro") (part "CPG151101S21 RF v1.0"))
    )
    (comp (ref "SW271")
      (value "CPG151101S21")
      (footprint "easyedapro:KEY-TH_CPG1511F01S0X_1")
      (fields (field (name "Manufacturer") "Kailh(凯华)"))
      (libsource (lib "easyedapro") (part "CPG151101S21 RF v1.0"))
    )
    (comp (ref "SW272")
      (value "CPG151101S21")
      (footprint "easyedapro:KEY-TH_CPG1511F01S0X_1")
      (fields (field (name "Manufacturer") "Kailh(凯华)"))
      (libsource (lib "easyedapro") (part "CPG151101S21 RF v1.0"))
    )
    (comp (ref "SW273")
      (value "CPG151101S21")
      (footprint "easyedapro:KEY-TH_CPG1511F01S0X_1")
      (fields (field (name "Manufacturer") "Kailh(凯华)"))
      (libsource (lib "easyedapro") (part "CPG151101S21 RF v1.0"))
    )
    (comp (ref "SW274")
      (value "CPG151101S21")
      (footprint "easyedapro:KEY-TH_CPG1511F01S0X_1")
      (fields (field (name "Manufacturer") "Kailh(凯华)"))
      (libsource (lib "easyedapro") (part "CPG151101S21 RF v1.0"))
    )
    (comp (ref "SW275")
      (value "CPG151101S21")
      (footprint "easyedapro:KEY-TH_CPG1511F01S0X_1")
      (fields (field (name "Manufacturer") "Kailh(凯华)"))
      (libsource (lib "easyedapro") (part "CPG151101S21 RF v1.0"))
    )
    (comp (ref "SW276")
      (value "CPG151101S21")
      (footprint "easyedapro:KEY-TH_CPG1511F01S0X_1")
      (fields (field (name "Manufacturer") "Kailh(凯华)"))
      (libsource (lib "easyedapro") (part "CPG151101S21 RF v1.0"))
    )
    (comp (ref "SW277")
      (value "CPG151101S21")
      (footprint "easyedapro:KEY-TH_CPG1511F01S0X_1")
      (fields (field (name "Manufacturer") "Kailh(凯华)"))
      (libsource (lib "easyedapro") (part "CPG151101S21 RF v1.0"))
    )
    (comp (ref "SW278")
      (value "CPG151101S21")
      (footprint "easyedapro:KEY-TH_CPG1511F01S0X_1")
      (fields (field (name "Manufacturer") "Kailh(凯华)"))
      (libsource (lib "easyedapro") (part "CPG151101S21 RF v1.0"))
    )
  )
  (nets
    (net (code "1") (name "+1V1") (class "Default")
      (node (ref "C107") (pin "2") (pinfunction "2_2") (pintype "unspecified"))
      (node (ref "C108") (pin "2") (pinfunction "2_2") (pintype "unspecified"))
      (node (ref "C109") (pin "2") (pinfunction "2_2") (pintype "unspecified"))
      (node (ref "U101") (pin "23") (pinfunction "DVDD_23") (pintype "bidirectional"))
      (node (ref "U101") (pin "45") (pinfunction "VREG_VOUT_45") (pintype "bidirectional"))
      (node (ref "U101") (pin "50") (pinfunction "DVDD_50") (pintype "bidirectional"))
    )
    (net (code "2") (name "+3V3") (class "Default")
      (node (ref "C101") (pin "2") (pinfunction "2_2") (pintype "unspecified"))
      (node (ref "C102") (pin "2") (pinfunction "2_2") (pintype "unspecified"))
      (node (ref "C103") (pin "2") (pinfunction "2_2") (pintype "unspecified"))
      (node (ref "C104") (pin "2") (pinfunction "2_2") (pintype "unspecified"))
      (node (ref "C106") (pin "2") (pinfunction "2_2") (pintype "unspecified"))
      (node (ref "C112") (pin "2") (pinfunction "2_2") (pintype "unspecified"))
      (node (ref "C113") (pin "2") (pinfunction "2_2") (pintype "unspecified"))
      (node (ref "C114") (pin "2") (pinfunction "2_2") (pintype "unspecified"))
      (node (ref "C115") (pin "2") (pinfunction "2_2") (pintype "unspecified"))
      (node (ref "C116") (pin "2") (pinfunction "2_2") (pintype "unspecified"))
      (node (ref "C126") (pin "2") (pinfunction "2_2") (pintype "unspecified"))
      (node (ref "C201") (pin "2") (pinfunction "2_2") (pintype "unspecified"))
      (node (ref "R101") (pin "1") (pinfunction "1_1") (pintype "input"))
      (node (ref "R104") (pin "2") (pinfunction "2_2") (pintype "input"))
      (node (ref "R122") (pin "2") (pinfunction "2_2") (pintype "input"))
      (node (ref "R123") (pin "2") (pinfunction "2_2") (pintype "input"))
      (node (ref "R201") (pin "2") (pinfunction "2_2") (pintype "input"))
      (node (ref "R202") (pin "2") (pinfunction "2_2") (pintype "input"))
      (node (ref "R223") (pin "2") (pinfunction "2_2") (pintype "input"))
      (node (ref "R224") (pin "2") (pinfunction "2_2") (pintype "input"))
      (node (ref "U101") (pin "1") (pinfunction "IOVDD_1") (pintype "bidirectional"))
      (node (ref "U101") (pin "10") (pinfunction "IOVDD_10") (pintype "bidirectional"))
      (node (ref "U101") (pin "22") (pinfunction "IOVDD_22") (pintype "bidirectional"))
      (node (ref "U101") (pin "33") (pinfunction "IOVDD_33") (pintype "bidirectional"))
      (node (ref "U101") (pin "42") (pinfunction "IOVDD_42") (pintype "bidirectional"))
      (node (ref "U101") (pin "44") (pinfunction "VREG_IN_44") (pintype "bidirectional"))
      (node (ref "U101") (pin "48") (pinfunction "USB_VDD_48") (pintype "bidirectional"))
      (node (ref "U101") (pin "49") (pinfunction "IOVDD_49") (pintype "bidirectional"))
      (node (ref "U102") (pin "3") (pinfunction "OUT_3") (pintype "unspecified"))
      (node (ref "U104") (pin "8") (pinfunction "VCC_8") (pintype "unspecified"))
    )
    (net (code "3") (name "+3V3_A") (class "Default")
      (node (ref "C105") (pin "2") (pinfunction "2_2") (pintype "unspecified"))
      (node (ref "R101") (pin "2") (pinfunction "2_2") (pintype "input"))
      (node (ref "U101") (pin "43") (pinfunction "ADC_AVDD_43") (pintype "bidirectional"))
    )
    (net (code "4") (name "+5V_USB") (class "Default")
      (node (ref "C111") (pin "2") (pinfunction "2_2") (pintype "unspecified"))
      (node (ref "C118") (pin "2") (pinfunction "2_2") (pintype "unspecified"))
      (node (ref "C119") (pin "2") (pinfunction "2_2") (pintype "unspecified"))
      (node (ref "D101") (pin "2") (pinfunction "2_2") (pintype "input"))
      (node (ref "D102") (pin "2") (pinfunction "2_2") (pintype "input"))
      (node (ref "J101") (pin "11") (pinfunction "VBUS_11") (pintype "unspecified"))
      (node (ref "J101") (pin "2") (pinfunction "VBUS_2") (pintype "unspecified"))
      (node (ref "U102") (pin "1") (pinfunction "IN_1") (pintype "unspecified"))
    )
    (net (code "5") (name "COL0") (class "Default")
      (node (ref "J201") (pin "1") (pinfunction "1_1") (pintype "input"))
      (node (ref "J204") (pin "1") (pinfunction "1_1") (pintype "input"))
      (node (ref "J207") (pin "1") (pinfunction "1_1") (pintype "input"))
      (node (ref "J240") (pin "1") (pinfunction "1_1") (pintype "input"))
      (node (ref "J243") (pin "1") (pinfunction "1_1") (pintype "input"))
      (node (ref "J246") (pin "1") (pinfunction "1_1") (pintype "input"))
      (node (ref "R108") (pin "2") (pinfunction "2_2") (pintype "input"))
    )
    (net (code "6") (name "COL0_R") (class "Default")
      (node (ref "R108") (pin "1") (pinfunction "1_1") (pintype "input"))
      (node (ref "U101") (pin "2") (pinfunction "GPIO0_2") (pintype "bidirectional"))
    )
    (net (code "7") (name "COL1") (class "Default")
      (node (ref "J202") (pin "1") (pinfunction "1_1") (pintype "input"))
      (node (ref "J205") (pin "1") (pinfunction "1_1") (pintype "input"))
      (node (ref "J208") (pin "1") (pinfunction "1_1") (pintype "input"))
      (node (ref "J241") (pin "1") (pinfunction "1_1") (pintype "input"))
      (node (ref "J244") (pin "1") (pinfunction "1_1") (pintype "input"))
      (node (ref "J247") (pin "1") (pinfunction "1_1") (pintype "input"))
      (node (ref "R110") (pin "2") (pinfunction "2_2") (pintype "input"))
    )
    (net (code "8") (name "COL1_R") (class "Default")
      (node (ref "R110") (pin "1") (pinfunction "1_1") (pintype "input"))
      (node (ref "U101") (pin "3") (pinfunction "GPIO1_3") (pintype "bidirectional"))
    )
    (net (code "9") (name "COL2") (class "Default")
      (node (ref "J203") (pin "1") (pinfunction "1_1") (pintype "input"))
      (node (ref "J206") (pin "1") (pinfunction "1_1") (pintype "input"))
      (node (ref "J209") (pin "1") (pinfunction "1_1") (pintype "input"))
      (node (ref "J242") (pin "1") (pinfunction "1_1") (pintype "input"))
      (node (ref "J245") (pin "1") (pinfunction "1_1") (pintype "input"))
      (node (ref "J248") (pin "1") (pinfunction "1_1") (pintype "input"))
      (node (ref "R112") (pin "2") (pinfunction "2_2") (pintype "input"))
    )
    (net (code "10") (name "COL2_R") (class "Default")
      (node (ref "R112") (pin "1") (pinfunction "1_1") (pintype "input"))
      (node (ref "U101") (pin "4") (pinfunction "GPIO2_4") (pintype "bidirectional"))
    )
    (net (code "11") (name "COL3") (class "Default")
      (node (ref "J210") (pin "1") (pinfunction "1_1") (pintype "input"))
      (node (ref "J213") (pin "1") (pinfunction "1_1") (pintype "input"))
      (node (ref "J216") (pin "1") (pinfunction "1_1") (pintype "input"))
      (node (ref "J249") (pin "1") (pinfunction "1_1") (pintype "input"))
      (node (ref "J252") (pin "1") (pinfunction "1_1") (pintype "input"))
      (node (ref "J255") (pin "1") (pinfunction "1_1") (pintype "input"))
      (node (ref "R113") (pin "2") (pinfunction "2_2") (pintype "input"))
    )
    (net (code "12") (name "COL3_R") (class "Default")
      (node (ref "R113") (pin "1") (pinfunction "1_1") (pintype "input"))
      (node (ref "U101") (pin "5") (pinfunction "GPIO3_5") (pintype "bidirectional"))
    )
    (net (code "13") (name "COL4") (class "Default")
      (node (ref "J211") (pin "1") (pinfunction "1_1") (pintype "input"))
      (node (ref "J214") (pin "1") (pinfunction "1_1") (pintype "input"))
      (node (ref "J217") (pin "1") (pinfunction "1_1") (pintype "input"))
      (node (ref "J250") (pin "1") (pinfunction "1_1") (pintype "input"))
      (node (ref "J253") (pin "1") (pinfunction "1_1") (pintype "input"))
      (node (ref "J256") (pin "1") (pinfunction "1_1") (pintype "input"))
      (node (ref "R208") (pin "2") (pinfunction "2_2") (pintype "input"))
    )
    (net (code "14") (name "COL4_R") (class "Default")
      (node (ref "R208") (pin "1") (pinfunction "1_1") (pintype "input"))
      (node (ref "U101") (pin "6") (pinfunction "GPIO4_6") (pintype "bidirectional"))
    )
    (net (code "15") (name "COL5") (class "Default")
      (node (ref "J212") (pin "1") (pinfunction "1_1") (pintype "input"))
      (node (ref "J215") (pin "1") (pinfunction "1_1") (pintype "input"))
      (node (ref "J218") (pin "1") (pinfunction "1_1") (pintype "input"))
      (node (ref "J251") (pin "1") (pinfunction "1_1") (pintype "input"))
      (node (ref "J254") (pin "1") (pinfunction "1_1") (pintype "input"))
      (node (ref "J257") (pin "1") (pinfunction "1_1") (pintype "input"))
      (node (ref "R209") (pin "2") (pinfunction "2_2") (pintype "input"))
    )
    (net (code "16") (name "COL5_R") (class "Default")
      (node (ref "R209") (pin "1") (pinfunction "1_1") (pintype "input"))
      (node (ref "U101") (pin "7") (pinfunction "GPIO5_7") (pintype "bidirectional"))
    )
    (net (code "17") (name "COL6") (class "Default")
      (node (ref "J219") (pin "1") (pinfunction "1_1") (pintype "input"))
      (node (ref "J222") (pin "1") (pinfunction "1_1") (pintype "input"))
      (node (ref "J225") (pin "1") (pinfunction "1_1") (pintype "input"))
      (node (ref "J258") (pin "1") (pinfunction "1_1") (pintype "input"))
      (node (ref "J261") (pin "1") (pinfunction "1_1") (pintype "input"))
      (node (ref "J264") (pin "1") (pinfunction "1_1") (pintype "input"))
      (node (ref "R210") (pin "2") (pinfunction "2_2") (pintype "input"))
    )
    (net (code "18") (name "COL6_R") (class "Default")
      (node (ref "R210") (pin "1") (pinfunction "1_1") (pintype "input"))
      (node (ref "U101") (pin "8") (pinfunction "GPIO6_8") (pintype "bidirectional"))
    )
    (net (code "19") (name "COL7") (class "Default")
      (node (ref "J220") (pin "1") (pinfunction "1_1") (pintype "input"))
      (node (ref "J223") (pin "1") (pinfunction "1_1") (pintype "input"))
      (node (ref "J226") (pin "1") (pinfunction "1_1") (pintype "input"))
      (node (ref "J259") (pin "1") (pinfunction "1_1") (pintype "input"))
      (node (ref "J262") (pin "1") (pinfunction "1_1") (pintype "input"))
      (node (ref "J265") (pin "1") (pinfunction "1_1") (pintype "input"))
      (node (ref "R211") (pin "2") (pinfunction "2_2") (pintype "input"))
    )
    (net (code "20") (name "COL7_R") (class "Default")
      (node (ref "R211") (pin "1") (pinfunction "1_1") (pintype "input"))
      (node (ref "U101") (pin "9") (pinfunction "GPIO7_9") (pintype "bidirectional"))
    )
    (net (code "21") (name "COL8") (class "Default")
      (node (ref "J221") (pin "1") (pinfunction "1_1") (pintype "input"))
      (node (ref "J224") (pin "1") (pinfunction "1_1") (pintype "input"))
      (node (ref "J227") (pin "1") (pinfunction "1_1") (pintype "input"))
      (node (ref "J260") (pin "1") (pinfunction "1_1") (pintype "input"))
      (node (ref "J263") (pin "1") (pinfunction "1_1") (pintype "input"))
      (node (ref "J266") (pin "1") (pinfunction "1_1") (pintype "input"))
      (node (ref "R212") (pin "2") (pinfunction "2_2") (pintype "input"))
    )
    (net (code "22") (name "COL8_R") (class "Default")
      (node (ref "R212") (pin "1") (pinfunction "1_1") (pintype "input"))
      (node (ref "U101") (pin "11") (pinfunction "GPIO8_11") (pintype "bidirectional"))
    )
    (net (code "23") (name "COL9") (class "Default")
      (node (ref "J228") (pin "1") (pinfunction "1_1") (pintype "input"))
      (node (ref "J231") (pin "1") (pinfunction "1_1") (pintype "input"))
      (node (ref "J234") (pin "1") (pinfunction "1_1") (pintype "input"))
      (node (ref "J267") (pin "1") (pinfunction "1_1") (pintype "input"))
      (node (ref "J270") (pin "1") (pinfunction "1_1") (pintype "input"))
      (node (ref "J273") (pin "1") (pinfunction "1_1") (pintype "input"))
      (node (ref "R213") (pin "2") (pinfunction "2_2") (pintype "input"))
    )
    (net (code "24") (name "COL9_R") (class "Default")
      (node (ref "R213") (pin "1") (pinfunction "1_1") (pintype "input"))
      (node (ref "U101") (pin "12") (pinfunction "GPIO9_12") (pintype "bidirectional"))
    )
    (net (code "25") (name "COL10") (class "Default")
      (node (ref "J229") (pin "1") (pinfunction "1_1") (pintype "input"))
      (node (ref "J232") (pin "1") (pinfunction "1_1") (pintype "input"))
      (node (ref "J235") (pin "1") (pinfunction "1_1") (pintype "input"))
      (node (ref "J268") (pin "1") (pinfunction "1_1") (pintype "input"))
      (node (ref "J271") (pin "1") (pinfunction "1_1") (pintype "input"))
      (node (ref "J274") (pin "1") (pinfunction "1_1") (pintype "input"))
      (node (ref "R214") (pin "2") (pinfunction "2_2") (pintype "input"))
    )
    (net (code "26") (name "COL10_R") (class "Default")
      (node (ref "R214") (pin "1") (pinfunction "1_1") (pintype "input"))
      (node (ref "U101") (pin "13") (pinfunction "GPIO10_13") (pintype "bidirectional"))
    )
    (net (code "27") (name "COL11") (class "Default")
      (node (ref "J230") (pin "1") (pinfunction "1_1") (pintype "input"))
      (node (ref "J233") (pin "1") (pinfunction "1_1") (pintype "input"))
      (node (ref "J236") (pin "1") (pinfunction "1_1") (pintype "input"))
      (node (ref "J269") (pin "1") (pinfunction "1_1") (pintype "input"))
      (node (ref "J272") (pin "1") (pinfunction "1_1") (pintype "input"))
      (node (ref "J275") (pin "1") (pinfunction "1_1") (pintype "input"))
      (node (ref "R215") (pin "2") (pinfunction "2_2") (pintype "input"))
    )
    (net (code "28") (name "COL11_R") (class "Default")
      (node (ref "R215") (pin "1") (pinfunction "1_1") (pintype "input"))
      (node (ref "U101") (pin "14") (pinfunction "GPIO11_14") (pintype "bidirectional"))
    )
    (net (code "29") (name "COL12") (class "Default")
      (node (ref "J237") (pin "1") (pinfunction "1_1") (pintype "input"))
      (node (ref "J238") (pin "1") (pinfunction "1_1") (pintype "input"))
      (node (ref "J239") (pin "1") (pinfunction "1_1") (pintype "input"))
      (node (ref "J276") (pin "1") (pinfunction "1_1") (pintype "input"))
      (node (ref "J277") (pin "1") (pinfunction "1_1") (pintype "input"))
      (node (ref "J278") (pin "1") (pinfunction "1_1") (pintype "input"))
      (node (ref "R216") (pin "2") (pinfunction "2_2") (pintype "input"))
    )
    (net (code "30") (name "COL12_R") (class "Default")
      (node (ref "R216") (pin "1") (pinfunction "1_1") (pintype "input"))
      (node (ref "U101") (pin "15") (pinfunction "GPIO12_15") (pintype "bidirectional"))
    )
    (net (code "31") (name "CON_USB_N") (class "Default")
      (node (ref "D103") (pin "2") (pinfunction "2_2") (pintype "input"))
      (node (ref "J101") (pin "5") (pinfunction "DN2_5") (pintype "unspecified"))
      (node (ref "J101") (pin "7") (pinfunction "DN1_7") (pintype "unspecified"))
      (node (ref "R109") (pin "1") (pinfunction "1_1") (pintype "input"))
    )
    (net (code "32") (name "CON_USB_P") (class "Default")
      (node (ref "D104") (pin "2") (pinfunction "2_2") (pintype "input"))
      (node (ref "J101") (pin "6") (pinfunction "DP1_6") (pintype "unspecified"))
      (node (ref "J101") (pin "8") (pinfunction "DP2_8") (pintype "unspecified"))
      (node (ref "R111") (pin "1") (pinfunction "1_1") (pintype "input"))
    )
    (net (code "33") (name "CS") (class "Default")
      (node (ref "FPC1") (pin "5") (pinfunction "5_5") (pintype "unspecified"))
      (node (ref "U101") (pin "32") (pinfunction "GPIO21_32") (pintype "bidirectional"))
    )
    (net (code "34") (name "ENC1_A") (class "Default")
      (node (ref "C203") (pin "2") (pinfunction "2_2") (pintype "input"))
      (node (ref "R205") (pin "1") (pinfunction "1_1") (pintype "input"))
      (node (ref "U101") (pin "30") (pinfunction "GPIO19_30") (pintype "bidirectional"))
    )
    (net (code "35") (name "ENC1_B") (class "Default")
      (node (ref "C204") (pin "2") (pinfunction "2_2") (pintype "input"))
      (node (ref "R207") (pin "1") (pinfunction "1_1") (pintype "input"))
      (node (ref "U101") (pin "31") (pinfunction "GPIO20_31") (pintype "bidirectional"))
    )
    (net (code "36") (name "GND") (class "Default")
      (node (ref "C101") (pin "1") (pinfunction "1_1") (pintype "unspecified"))
      (node (ref "C102") (pin "1") (pinfunction "1_1") (pintype "unspecified"))
      (node (ref "C103") (pin "1") (pinfunction "1_1") (pintype "unspecified"))
      (node (ref "C104") (pin "1") (pinfunction "1_1") (pintype "unspecified"))
      (node (ref "C105") (pin "1") (pinfunction "1_1") (pintype "unspecified"))
      (node (ref "C106") (pin "1") (pinfunction "1_1") (pintype "unspecified"))
      (node (ref "C107") (pin "1") (pinfunction "1_1") (pintype "unspecified"))
      (node (ref "C108") (pin "1") (pinfunction "1_1") (pintype "unspecified"))
      (node (ref "C109") (pin "1") (pinfunction "1_1") (pintype "unspecified"))
      (node (ref "C111") (pin "1") (pinfunction "1_1") (pintype "unspecified"))
      (node (ref "C112") (pin "1") (pinfunction "1_1") (pintype "unspecified"))
      (node (ref "C113") (pin "1") (pinfunction "1_1") (pintype "unspecified"))
      (node (ref "C114") (pin "1") (pinfunction "1_1") (pintype "unspecified"))
      (node (ref "C115") (pin "1") (pinfunction "1_1") (pintype "unspecified"))
      (node (ref "C116") (pin "1") (pinfunction "1_1") (pintype "unspecified"))
      (node (ref "C118") (pin "1") (pinfunction "1_1") (pintype "unspecified"))
      (node (ref "C119") (pin "1") (pinfunction "1_1") (pintype "unspecified"))
      (node (ref "C123") (pin "2") (pinfunction "2_2") (pintype "unspecified"))
      (node (ref "C124") (pin "2") (pinfunction "2_2") (pintype "unspecified"))
      (node (ref "C126") (pin "1") (pinfunction "1_1") (pintype "unspecified"))
      (node (ref "C127") (pin "1") (pinfunction "1_1") (pintype "unspecified"))
      (node (ref "C201") (pin "1") (pinfunction "1_1") (pintype "unspecified"))
      (node (ref "C203") (pin "1") (pinfunction "1_1") (pintype "input"))
      (node (ref "C204") (pin "1") (pinfunction "1_1") (pintype "input"))
      (node (ref "D101") (pin "1") (pinfunction "1_1") (pintype "input"))
      (node (ref "D102") (pin "1") (pinfunction "1_1") (pintype "input"))
      (node (ref "D103") (pin "1") (pinfunction "1_1") (pintype "input"))
      (node (ref "D104") (pin "1") (pinfunction "1_1") (pintype "input"))
      (node (ref "ENC201") (pin "3") (pinfunction "3_3") (pintype "input"))
      (node (ref "ENC201") (pin "4") (pinfunction "4_4") (pintype "input"))
      (node (ref "ENC201") (pin "C") (pinfunction "C_C") (pintype "input"))
      (node (ref "FPC1") (pin "10") (pinfunction "10_10") (pintype "unspecified"))
      (node (ref "FPC1") (pin "8") (pinfunction "8_8") (pintype "unspecified"))
      (node (ref "J101") (pin "1") (pinfunction "GND_1") (pintype "unspecified"))
      (node (ref "J101") (pin "12") (pinfunction "GND_12") (pintype "unspecified"))
      (node (ref "J101") (pin "13") (pinfunction "SHELL_13") (pintype "unspecified"))
      (node (ref "J101") (pin "14") (pinfunction "SHELL_14") (pintype "unspecified"))
      (node (ref "J102") (pin "2") (pinfunction "2_2") (pintype "input"))
      (node (ref "LED102") (pin "2") (pinfunction "K_2") (pintype "unspecified"))
      (node (ref "MH201") (pin "1") (pinfunction "1_1") (pintype "input"))
      (node (ref "MH202") (pin "1") (pinfunction "1_1") (pintype "input"))
      (node (ref "MH203") (pin "1") (pinfunction "1_1") (pintype "input"))
      (node (ref "MH204") (pin "1") (pinfunction "1_1") (pintype "input"))
      (node (ref "MH205") (pin "1") (pinfunction "1_1") (pintype "input"))
      (node (ref "MH206") (pin "1") (pinfunction "1_1") (pintype "input"))
      (node (ref "MH207") (pin "1") (pinfunction "1_1") (pintype "input"))
      (node (ref "MH208") (pin "1") (pinfunction "1_1") (pintype "input"))
      (node (ref "R118") (pin "1") (pinfunction "1_1") (pintype "input"))
      (node (ref "R119") (pin "1") (pinfunction "1_1") (pintype "input"))
      (node (ref "SW101") (pin "1") (pinfunction "A_1") (pintype "input"))
      (node (ref "SW101") (pin "2") (pinfunction "B_2") (pintype "input"))
      (node (ref "SW102") (pin "1") (pinfunction "A_1") (pintype "input"))
      (node (ref "SW102") (pin "2") (pinfunction "B_2") (pintype "input"))
      (node (ref "U101") (pin "19") (pinfunction "TESTEN_19") (pintype "unspecified"))
      (node (ref "U101") (pin "57") (pinfunction "GND_57") (pintype "bidirectional"))
      (node (ref "U102") (pin "2") (pinfunction "GND_2") (pintype "unspecified"))
      (node (ref "U102") (pin "4") (pinfunction "GND_4") (pintype "unspecified"))
      (node (ref "U104") (pin "4") (pinfunction "GND_4") (pintype "unspecified"))
      (node (ref "Y101") (pin "2") (pinfunction "GND_2") (pintype "input"))
      (node (ref "Y101") (pin "4") (pinfunction "GND_4") (pintype "input"))
    )
    (net (code "37") (name "Net-(D201-A)") (class "Default")
      (node (ref "D201") (pin "2") (pinfunction "A_2") (pintype "input"))
      (node (ref "J201") (pin "2") (pinfunction "2_2") (pintype "input"))
    )
    (net (code "38") (name "Net-(D202-A)") (class "Default")
      (node (ref "D202") (pin "2") (pinfunction "A_2") (pintype "input"))
      (node (ref "J202") (pin "2") (pinfunction "2_2") (pintype "input"))
    )
    (net (code "39") (name "Net-(D203-A)") (class "Default")
      (node (ref "D203") (pin "2") (pinfunction "A_2") (pintype "input"))
      (node (ref "J203") (pin "2") (pinfunction "2_2") (pintype "input"))
    )
    (net (code "40") (name "Net-(D204-A)") (class "Default")
      (node (ref "D204") (pin "2") (pinfunction "A_2") (pintype "input"))
      (node (ref "J204") (pin "2") (pinfunction "2_2") (pintype "input"))
    )
    (net (code "41") (name "Net-(D205-A)") (class "Default")
      (node (ref "D205") (pin "2") (pinfunction "A_2") (pintype "input"))
      (node (ref "J205") (pin "2") (pinfunction "2_2") (pintype "input"))
    )
    (net (code "42") (name "Net-(D206-A)") (class "Default")
      (node (ref "D206") (pin "2") (pinfunction "A_2") (pintype "input"))
      (node (ref "J206") (pin "2") (pinfunction "2_2") (pintype "input"))
    )
    (net (code "43") (name "Net-(D207-A)") (class "Default")
      (node (ref "D207") (pin "2") (pinfunction "A_2") (pintype "input"))
      (node (ref "J207") (pin "2") (pinfunction "2_2") (pintype "input"))
    )
    (net (code "44") (name "Net-(D208-A)") (class "Default")
      (node (ref "D208") (pin "2") (pinfunction "A_2") (pintype "input"))
      (node (ref "J208") (pin "2") (pinfunction "2_2") (pintype "input"))
    )
    (net (code "45") (name "Net-(D209-A)") (class "Default")
      (node (ref "D209") (pin "2") (pinfunction "A_2") (pintype "input"))
      (node (ref "J209") (pin "2") (pinfunction "2_2") (pintype "input"))
    )
    (net (code "46") (name "Net-(D213-A)") (class "Default")
      (node (ref "D213") (pin "2") (pinfunction "A_2") (pintype "input"))
      (node (ref "J210") (pin "2") (pinfunction "2_2") (pintype "input"))
    )
    (net (code "47") (name "Net-(D214-A)") (class "Default")
      (node (ref "D214") (pin "2") (pinfunction "A_2") (pintype "input"))
      (node (ref "J211") (pin "2") (pinfunction "2_2") (pintype "input"))
    )
    (net (code "48") (name "Net-(D215-A)") (class "Default")
      (node (ref "D215") (pin "2") (pinfunction "A_2") (pintype "input"))
      (node (ref "J212") (pin "2") (pinfunction "2_2") (pintype "input"))
    )
    (net (code "49") (name "Net-(D216-A)") (class "Default")
      (node (ref "D216") (pin "2") (pinfunction "A_2") (pintype "input"))
      (node (ref "J213") (pin "2") (pinfunction "2_2") (pintype "input"))
    )
    (net (code "50") (name "Net-(D217-A)") (class "Default")
      (node (ref "D217") (pin "2") (pinfunction "A_2") (pintype "input"))
      (node (ref "J214") (pin "2") (pinfunction "2_2") (pintype "input"))
    )
    (net (code "51") (name "Net-(D218-A)") (class "Default")
      (node (ref "D218") (pin "2") (pinfunction "A_2") (pintype "input"))
      (node (ref "J215") (pin "2") (pinfunction "2_2") (pintype "input"))
    )
    (net (code "52") (name "Net-(D219-A)") (class "Default")
      (node (ref "D219") (pin "2") (pinfunction "A_2") (pintype "input"))
      (node (ref "J216") (pin "2") (pinfunction "2_2") (pintype "input"))
    )
    (net (code "53") (name "Net-(D220-A)") (class "Default")
      (node (ref "D220") (pin "2") (pinfunction "A_2") (pintype "input"))
      (node (ref "J217") (pin "2") (pinfunction "2_2") (pintype "input"))
    )
    (net (code "54") (name "Net-(D221-A)") (class "Default")
      (node (ref "D221") (pin "2") (pinfunction "A_2") (pintype "input"))
      (node (ref "J218") (pin "2") (pinfunction "2_2") (pintype "input"))
    )
    (net (code "55") (name "Net-(D225-A)") (class "Default")
      (node (ref "D225") (pin "2") (pinfunction "A_2") (pintype "input"))
      (node (ref "J219") (pin "2") (pinfunction "2_2") (pintype "input"))
    )
    (net (code "56") (name "Net-(D226-A)") (class "Default")
      (node (ref "D226") (pin "2") (pinfunction "A_2") (pintype "input"))
      (node (ref "J220") (pin "2") (pinfunction "2_2") (pintype "input"))
    )
    (net (code "57") (name "Net-(D227-A)") (class "Default")
      (node (ref "D227") (pin "2") (pinfunction "A_2") (pintype "input"))
      (node (ref "J221") (pin "2") (pinfunction "2_2") (pintype "input"))
    )
    (net (code "58") (name "Net-(D228-A)") (class "Default")
      (node (ref "D228") (pin "2") (pinfunction "A_2") (pintype "input"))
      (node (ref "J222") (pin "2") (pinfunction "2_2") (pintype "input"))
    )
    (net (code "59") (name "Net-(D229-A)") (class "Default")
      (node (ref "D229") (pin "2") (pinfunction "A_2") (pintype "input"))
      (node (ref "J223") (pin "2") (pinfunction "2_2") (pintype "input"))
    )
    (net (code "60") (name "Net-(D230-A)") (class "Default")
      (node (ref "D230") (pin "2") (pinfunction "A_2") (pintype "input"))
      (node (ref "J224") (pin "2") (pinfunction "2_2") (pintype "input"))
    )
    (net (code "61") (name "Net-(D231-A)") (class "Default")
      (node (ref "D231") (pin "2") (pinfunction "A_2") (pintype "input"))
      (node (ref "J225") (pin "2") (pinfunction "2_2") (pintype "input"))
    )
    (net (code "62") (name "Net-(D232-A)") (class "Default")
      (node (ref "D232") (pin "2") (pinfunction "A_2") (pintype "input"))
      (node (ref "J226") (pin "2") (pinfunction "2_2") (pintype "input"))
    )
    (net (code "63") (name "Net-(D233-A)") (class "Default")
      (node (ref "D233") (pin "2") (pinfunction "A_2") (pintype "input"))
      (node (ref "J227") (pin "2") (pinfunction "2_2") (pintype "input"))
    )
    (net (code "64") (name "Net-(D237-A)") (class "Default")
      (node (ref "D237") (pin "2") (pinfunction "A_2") (pintype "input"))
      (node (ref "J228") (pin "2") (pinfunction "2_2") (pintype "input"))
    )
    (net (code "65") (name "Net-(D238-A)") (class "Default")
      (node (ref "D238") (pin "2") (pinfunction "A_2") (pintype "input"))
      (node (ref "J229") (pin "2") (pinfunction "2_2") (pintype "input"))
    )
    (net (code "66") (name "Net-(D239-A)") (class "Default")
      (node (ref "D239") (pin "2") (pinfunction "A_2") (pintype "input"))
      (node (ref "J230") (pin "2") (pinfunction "2_2") (pintype "input"))
    )
    (net (code "67") (name "Net-(D240-A)") (class "Default")
      (node (ref "D240") (pin "2") (pinfunction "A_2") (pintype "input"))
      (node (ref "J231") (pin "2") (pinfunction "2_2") (pintype "input"))
    )
    (net (code "68") (name "Net-(D241-A)") (class "Default")
      (node (ref "D241") (pin "2") (pinfunction "A_2") (pintype "input"))
      (node (ref "J232") (pin "2") (pinfunction "2_2") (pintype "input"))
    )
    (net (code "69") (name "Net-(D242-A)") (class "Default")
      (node (ref "D242") (pin "2") (pinfunction "A_2") (pintype "input"))
      (node (ref "J233") (pin "2") (pinfunction "2_2") (pintype "input"))
    )
    (net (code "70") (name "Net-(D243-A)") (class "Default")
      (node (ref "D243") (pin "2") (pinfunction "A_2") (pintype "input"))
      (node (ref "J234") (pin "2") (pinfunction "2_2") (pintype "input"))
    )
    (net (code "71") (name "Net-(D244-A)") (class "Default")
      (node (ref "D244") (pin "2") (pinfunction "A_2") (pintype "input"))
      (node (ref "J235") (pin "2") (pinfunction "2_2") (pintype "input"))
    )
    (net (code "72") (name "Net-(D245-A)") (class "Default")
      (node (ref "D245") (pin "2") (pinfunction "A_2") (pintype "input"))
      (node (ref "J236") (pin "2") (pinfunction "2_2") (pintype "input"))
    )
    (net (code "73") (name "Net-(D249-A)") (class "Default")
      (node (ref "D249") (pin "2") (pinfunction "A_2") (pintype "input"))
      (node (ref "J237") (pin "2") (pinfunction "2_2") (pintype "input"))
    )
    (net (code "74") (name "Net-(D250-A)") (class "Default")
      (node (ref "D250") (pin "2") (pinfunction "A_2") (pintype "input"))
      (node (ref "J238") (pin "2") (pinfunction "2_2") (pintype "input"))
    )
    (net (code "75") (name "Net-(D251-A)") (class "Default")
      (node (ref "D251") (pin "2") (pinfunction "A_2") (pintype "input"))
      (node (ref "J239") (pin "2") (pinfunction "2_2") (pintype "input"))
    )
    (net (code "76") (name "Net-(D252-A)") (class "Default")
      (node (ref "D252") (pin "2") (pinfunction "A_2") (pintype "input"))
      (node (ref "J240") (pin "2") (pinfunction "2_2") (pintype "input"))
    )
    (net (code "77") (name "Net-(D253-A)") (class "Default")
      (node (ref "D253") (pin "2") (pinfunction "A_2") (pintype "input"))
      (node (ref "J241") (pin "2") (pinfunction "2_2") (pintype "input"))
    )
    (net (code "78") (name "Net-(D254-A)") (class "Default")
      (node (ref "D254") (pin "2") (pinfunction "A_2") (pintype "input"))
      (node (ref "J242") (pin "2") (pinfunction "2_2") (pintype "input"))
    )
    (net (code "79") (name "Net-(D255-A)") (class "Default")
      (node (ref "D255") (pin "2") (pinfunction "A_2") (pintype "input"))
      (node (ref "J243") (pin "2") (pinfunction "2_2") (pintype "input"))
    )
    (net (code "80") (name "Net-(D256-A)") (class "Default")
      (node (ref "D256") (pin "2") (pinfunction "A_2") (pintype "input"))
      (node (ref "J244") (pin "2") (pinfunction "2_2") (pintype "input"))
    )
    (net (code "81") (name "Net-(D257-A)") (class "Default")
      (node (ref "D257") (pin "2") (pinfunction "A_2") (pintype "input"))
      (node (ref "J245") (pin "2") (pinfunction "2_2") (pintype "input"))
    )
    (net (code "82") (name "Net-(D258-A)") (class "Default")
      (node (ref "D258") (pin "2") (pinfunction "A_2") (pintype "input"))
      (node (ref "J246") (pin "2") (pinfunction "2_2") (pintype "input"))
    )
    (net (code "83") (name "Net-(D259-A)") (class "Default")
      (node (ref "D259") (pin "2") (pinfunction "A_2") (pintype "input"))
      (node (ref "J247") (pin "2") (pinfunction "2_2") (pintype "input"))
    )
    (net (code "84") (name "Net-(D260-A)") (class "Default")
      (node (ref "D260") (pin "2") (pinfunction "A_2") (pintype "input"))
      (node (ref "J248") (pin "2") (pinfunction "2_2") (pintype "input"))
    )
    (net (code "85") (name "Net-(D261-A)") (class "Default")
      (node (ref "D261") (pin "2") (pinfunction "A_2") (pintype "input"))
      (node (ref "J249") (pin "2") (pinfunction "2_2") (pintype "input"))
    )
    (net (code "86") (name "Net-(D262-A)") (class "Default")
      (node (ref "D262") (pin "2") (pinfunction "A_2") (pintype "input"))
      (node (ref "J250") (pin "2") (pinfunction "2_2") (pintype "input"))
    )
    (net (code "87") (name "Net-(D263-A)") (class "Default")
      (node (ref "D263") (pin "2") (pinfunction "A_2") (pintype "input"))
      (node (ref "J251") (pin "2") (pinfunction "2_2") (pintype "input"))
    )
    (net (code "88") (name "Net-(D264-A)") (class "Default")
      (node (ref "D264") (pin "2") (pinfunction "A_2") (pintype "input"))
      (node (ref "J252") (pin "2") (pinfunction "2_2") (pintype "input"))
    )
    (net (code "89") (name "Net-(D265-A)") (class "Default")
      (node (ref "D265") (pin "2") (pinfunction "A_2") (pintype "input"))
      (node (ref "J253") (pin "2") (pinfunction "2_2") (pintype "input"))
    )
    (net (code "90") (name "Net-(D266-A)") (class "Default")
      (node (ref "D266") (pin "2") (pinfunction "A_2") (pintype "input"))
      (node (ref "J254") (pin "2") (pinfunction "2_2") (pintype "input"))
    )
    (net (code "91") (name "Net-(D267-A)") (class "Default")
      (node (ref "D267") (pin "2") (pinfunction "A_2") (pintype "input"))
      (node (ref "J255") (pin "2") (pinfunction "2_2") (pintype "input"))
    )
    (net (code "92") (name "Net-(D268-A)") (class "Default")
      (node (ref "D268") (pin "2") (pinfunction "A_2") (pintype "input"))
      (node (ref "J256") (pin "2") (pinfunction "2_2") (pintype "input"))
    )
    (net (code "93") (name "Net-(D269-A)") (class "Default")
      (node (ref "D269") (pin "2") (pinfunction "A_2") (pintype "input"))
      (node (ref "J257") (pin "2") (pinfunction "2_2") (pintype "input"))
    )
    (net (code "94") (name "Net-(D270-A)") (class "Default")
      (node (ref "D270") (pin "2") (pinfunction "A_2") (pintype "input"))
      (node (ref "J258") (pin "2") (pinfunction "2_2") (pintype "input"))
    )
    (net (code "95") (name "Net-(D271-A)") (class "Default")
      (node (ref "D271") (pin "2") (pinfunction "A_2") (pintype "input"))
      (node (ref "J259") (pin "2") (pinfunction "2_2") (pintype "input"))
    )
    (net (code "96") (name "Net-(D272-A)") (class "Default")
      (node (ref "D272") (pin "2") (pinfunction "A_2") (pintype "input"))
      (node (ref "J260") (pin "2") (pinfunction "2_2") (pintype "input"))
    )
    (net (code "97") (name "Net-(D273-A)") (class "Default")
      (node (ref "D273") (pin "2") (pinfunction "A_2") (pintype "input"))
      (node (ref "J261") (pin "2") (pinfunction "2_2") (pintype "input"))
    )
    (net (code "98") (name "Net-(D274-A)") (class "Default")
      (node (ref "D274") (pin "2") (pinfunction "A_2") (pintype "input"))
      (node (ref "J262") (pin "2") (pinfunction "2_2") (pintype "input"))
    )
    (net (code "99") (name "Net-(D275-A)") (class "Default")
      (node (ref "D275") (pin "2") (pinfunction "A_2") (pintype "input"))
      (node (ref "J263") (pin "2") (pinfunction "2_2") (pintype "input"))
    )
    (net (code "100") (name "Net-(D276-A)") (class "Default")
      (node (ref "D276") (pin "2") (pinfunction "A_2") (pintype "input"))
      (node (ref "J264") (pin "2") (pinfunction "2_2") (pintype "input"))
    )
    (net (code "101") (name "Net-(D277-A)") (class "Default")
      (node (ref "D277") (pin "2") (pinfunction "A_2") (pintype "input"))
      (node (ref "J265") (pin "2") (pinfunction "2_2") (pintype "input"))
    )
    (net (code "102") (name "Net-(D278-A)") (class "Default")
      (node (ref "D278") (pin "2") (pinfunction "A_2") (pintype "input"))
      (node (ref "J266") (pin "2") (pinfunction "2_2") (pintype "input"))
    )
    (net (code "103") (name "Net-(D279-A)") (class "Default")
      (node (ref "D279") (pin "2") (pinfunction "A_2") (pintype "input"))
      (node (ref "J267") (pin "2") (pinfunction "2_2") (pintype "input"))
    )
    (net (code "104") (name "Net-(D280-A)") (class "Default")
      (node (ref "D280") (pin "2") (pinfunction "A_2") (pintype "input"))
      (node (ref "J268") (pin "2") (pinfunction "2_2") (pintype "input"))
    )
    (net (code "105") (name "Net-(D281-A)") (class "Default")
      (node (ref "D281") (pin "2") (pinfunction "A_2") (pintype "input"))
      (node (ref "J269") (pin "2") (pinfunction "2_2") (pintype "input"))
    )
    (net (code "106") (name "Net-(D282-A)") (class "Default")
      (node (ref "D282") (pin "2") (pinfunction "A_2") (pintype "input"))
      (node (ref "J270") (pin "2") (pinfunction "2_2") (pintype "input"))
    )
    (net (code "107") (name "Net-(D283-A)") (class "Default")
      (node (ref "D283") (pin "2") (pinfunction "A_2") (pintype "input"))
      (node (ref "J271") (pin "2") (pinfunction "2_2") (pintype "input"))
    )
    (net (code "108") (name "Net-(D284-A)") (class "Default")
      (node (ref "D284") (pin "2") (pinfunction "A_2") (pintype "input"))
      (node (ref "J272") (pin "2") (pinfunction "2_2") (pintype "input"))
    )
    (net (code "109") (name "Net-(D285-A)") (class "Default")
      (node (ref "D285") (pin "2") (pinfunction "A_2") (pintype "input"))
      (node (ref "J273") (pin "2") (pinfunction "2_2") (pintype "input"))
    )
    (net (code "110") (name "Net-(D286-A)") (class "Default")
      (node (ref "D286") (pin "2") (pinfunction "A_2") (pintype "input"))
      (node (ref "J274") (pin "2") (pinfunction "2_2") (pintype "input"))
    )
    (net (code "111") (name "Net-(D287-A)") (class "Default")
      (node (ref "D287") (pin "2") (pinfunction "A_2") (pintype "input"))
      (node (ref "J275") (pin "2") (pinfunction "2_2") (pintype "input"))
    )
    (net (code "112") (name "Net-(D288-A)") (class "Default")
      (node (ref "D288") (pin "2") (pinfunction "A_2") (pintype "input"))
      (node (ref "J276") (pin "2") (pinfunction "2_2") (pintype "input"))
    )
    (net (code "113") (name "Net-(D289-A)") (class "Default")
      (node (ref "D289") (pin "2") (pinfunction "A_2") (pintype "input"))
      (node (ref "J277") (pin "2") (pinfunction "2_2") (pintype "input"))
    )
    (net (code "114") (name "Net-(D290-A)") (class "Default")
      (node (ref "D290") (pin "2") (pinfunction "A_2") (pintype "input"))
      (node (ref "J278") (pin "2") (pinfunction "2_2") (pintype "input"))
    )
    (net (code "115") (name "Net-(ENC201-PadA)") (class "Default")
      (node (ref "ENC201") (pin "A") (pinfunction "A_A") (pintype "input"))
      (node (ref "R201") (pin "1") (pinfunction "1_1") (pintype "input"))
      (node (ref "R205") (pin "2") (pinfunction "2_2") (pintype "input"))
    )
    (net (code "116") (name "Net-(ENC201-PadB)") (class "Default")
      (node (ref "ENC201") (pin "B") (pinfunction "B_B") (pintype "input"))
      (node (ref "R202") (pin "1") (pinfunction "1_1") (pintype "input"))
      (node (ref "R207") (pin "2") (pinfunction "2_2") (pintype "input"))
    )
    (net (code "117") (name "Net-(FPC1-Pad7)") (class "Default")
      (node (ref "FPC1") (pin "7") (pinfunction "7_7") (pintype "unspecified"))
      (node (ref "R223") (pin "1") (pinfunction "1_1") (pintype "input"))
    )
    (net (code "118") (name "Net-(FPC1-Pad9)") (class "Default")
      (node (ref "FPC1") (pin "9") (pinfunction "9_9") (pintype "unspecified"))
      (node (ref "R224") (pin "1") (pinfunction "1_1") (pintype "input"))
    )
    (net (code "119") (name "Net-(J101-CC1)") (class "Default")
      (node (ref "J101") (pin "4") (pinfunction "CC1_4") (pintype "unspecified"))
      (node (ref "R119") (pin "2") (pinfunction "2_2") (pintype "input"))
    )
    (net (code "120") (name "Net-(J101-CC2)") (class "Default")
      (node (ref "J101") (pin "10") (pinfunction "CC2_10") (pintype "unspecified"))
      (node (ref "R118") (pin "2") (pinfunction "2_2") (pintype "input"))
    )
    (net (code "121") (name "Net-(LED102-A)") (class "Default")
      (node (ref "LED102") (pin "1") (pinfunction "A_1") (pintype "unspecified"))
      (node (ref "R104") (pin "1") (pinfunction "1_1") (pintype "input"))
    )
    (net (code "122") (name "Net-(SW101-C)") (class "Default")
      (node (ref "R122") (pin "1") (pinfunction "1_1") (pintype "input"))
      (node (ref "R124") (pin "1") (pinfunction "1_1") (pintype "input"))
      (node (ref "SW101") (pin "3") (pinfunction "C_3") (pintype "input"))
      (node (ref "SW101") (pin "4") (pinfunction "D_4") (pintype "input"))
    )
    (net (code "123") (name "Net-(SW102-C)") (class "Default")
      (node (ref "R123") (pin "1") (pinfunction "1_1") (pintype "input"))
      (node (ref "R125") (pin "1") (pinfunction "1_1") (pintype "input"))
      (node (ref "SW102") (pin "3") (pinfunction "C_3") (pintype "input"))
      (node (ref "SW102") (pin "4") (pinfunction "D_4") (pintype "input"))
    )
    (net (code "124") (name "QSPI_SCLK") (class "Default")
      (node (ref "U101") (pin "52") (pinfunction "QSPI_SCLK_52") (pintype "output"))
      (node (ref "U104") (pin "6") (pinfunction "CLK_6") (pintype "unspecified"))
    )
    (net (code "125") (name "QSPI_SD0") (class "Default")
      (node (ref "U101") (pin "53") (pinfunction "QSPI_SD0_53") (pintype "bidirectional"))
      (node (ref "U104") (pin "5") (pinfunction "DI_5") (pintype "unspecified"))
    )
    (net (code "126") (name "QSPI_SD1") (class "Default")
      (node (ref "U101") (pin "55") (pinfunction "QSPI_SD1_55") (pintype "bidirectional"))
      (node (ref "U104") (pin "2") (pinfunction "DO_2") (pintype "unspecified"))
    )
    (net (code "127") (name "QSPI_SD2") (class "Default")
      (node (ref "U101") (pin "54") (pinfunction "QSPI_SD2_54") (pintype "bidirectional"))
      (node (ref "U104") (pin "3") (pinfunction "IO2_3") (pintype "unspecified"))
    )
    (net (code "128") (name "QSPI_SD3") (class "Default")
      (node (ref "U101") (pin "51") (pinfunction "QSPI_SD3_51") (pintype "bidirectional"))
      (node (ref "U104") (pin "7") (pinfunction "IO3_7") (pintype "unspecified"))
    )
    (net (code "129") (name "QSPI_SS") (class "Default")
      (node (ref "R124") (pin "2") (pinfunction "2_2") (pintype "input"))
      (node (ref "U101") (pin "56") (pinfunction "QSPI_SS_56") (pintype "bidirectional"))
      (node (ref "U104") (pin "1") (pinfunction "CS#_1") (pintype "unspecified"))
    )
    (net (code "130") (name "RESET_N") (class "Default")
      (node (ref "C127") (pin "2") (pinfunction "2_2") (pintype "unspecified"))
      (node (ref "R125") (pin "2") (pinfunction "2_2") (pintype "input"))
      (node (ref "U101") (pin "26") (pinfunction "RUN_26") (pintype "input"))
    )
    (net (code "131") (name "ROW0") (class "Default")
      (node (ref "D201") (pin "1") (pinfunction "K_1") (pintype "input"))
      (node (ref "D202") (pin "1") (pinfunction "K_1") (pintype "input"))
      (node (ref "D203") (pin "1") (pinfunction "K_1") (pintype "input"))
      (node (ref "D213") (pin "1") (pinfunction "K_1") (pintype "input"))
      (node (ref "D214") (pin "1") (pinfunction "K_1") (pintype "input"))
      (node (ref "D215") (pin "1") (pinfunction "K_1") (pintype "input"))
      (node (ref "D225") (pin "1") (pinfunction "K_1") (pintype "input"))
      (node (ref "D226") (pin "1") (pinfunction "K_1") (pintype "input"))
      (node (ref "D227") (pin "1") (pinfunction "K_1") (pintype "input"))
      (node (ref "D237") (pin "1") (pinfunction "K_1") (pintype "input"))
      (node (ref "D238") (pin "1") (pinfunction "K_1") (pintype "input"))
      (node (ref "D239") (pin "1") (pinfunction "K_1") (pintype "input"))
      (node (ref "D249") (pin "1") (pinfunction "K_1") (pintype "input"))
      (node (ref "R217") (pin "2") (pinfunction "2_2") (pintype "input"))
    )
    (net (code "132") (name "ROW0_R") (class "Default")
      (node (ref "R217") (pin "1") (pinfunction "1_1") (pintype "input"))
      (node (ref "U101") (pin "16") (pinfunction "GPIO13_16") (pintype "bidirectional"))
    )
    (net (code "133") (name "ROW1") (class "Default")
      (node (ref "D204") (pin "1") (pinfunction "K_1") (pintype "input"))
      (node (ref "D205") (pin "1") (pinfunction "K_1") (pintype "input"))
      (node (ref "D206") (pin "1") (pinfunction "K_1") (pintype "input"))
      (node (ref "D216") (pin "1") (pinfunction "K_1") (pintype "input"))
      (node (ref "D217") (pin "1") (pinfunction "K_1") (pintype "input"))
      (node (ref "D218") (pin "1") (pinfunction "K_1") (pintype "input"))
      (node (ref "D228") (pin "1") (pinfunction "K_1") (pintype "input"))
      (node (ref "D229") (pin "1") (pinfunction "K_1") (pintype "input"))
      (node (ref "D230") (pin "1") (pinfunction "K_1") (pintype "input"))
      (node (ref "D240") (pin "1") (pinfunction "K_1") (pintype "input"))
      (node (ref "D241") (pin "1") (pinfunction "K_1") (pintype "input"))
      (node (ref "D242") (pin "1") (pinfunction "K_1") (pintype "input"))
      (node (ref "D250") (pin "1") (pinfunction "K_1") (pintype "input"))
      (node (ref "R218") (pin "2") (pinfunction "2_2") (pintype "input"))
    )
    (net (code "134") (name "ROW1_R") (class "Default")
      (node (ref "R218") (pin "1") (pinfunction "1_1") (pintype "input"))
      (node (ref "U101") (pin "17") (pinfunction "GPIO14_17") (pintype "bidirectional"))
    )
    (net (code "135") (name "ROW2") (class "Default")
      (node (ref "D207") (pin "1") (pinfunction "K_1") (pintype "input"))
      (node (ref "D208") (pin "1") (pinfunction "K_1") (pintype "input"))
      (node (ref "D209") (pin "1") (pinfunction "K_1") (pintype "input"))
      (node (ref "D219") (pin "1") (pinfunction "K_1") (pintype "input"))
      (node (ref "D220") (pin "1") (pinfunction "K_1") (pintype "input"))
      (node (ref "D221") (pin "1") (pinfunction "K_1") (pintype "input"))
      (node (ref "D231") (pin "1") (pinfunction "K_1") (pintype "input"))
      (node (ref "D232") (pin "1") (pinfunction "K_1") (pintype "input"))
      (node (ref "D233") (pin "1") (pinfunction "K_1") (pintype "input"))
      (node (ref "D243") (pin "1") (pinfunction "K_1") (pintype "input"))
      (node (ref "D244") (pin "1") (pinfunction "K_1") (pintype "input"))
      (node (ref "D245") (pin "1") (pinfunction "K_1") (pintype "input"))
      (node (ref "D251") (pin "1") (pinfunction "K_1") (pintype "input"))
      (node (ref "R219") (pin "2") (pinfunction "2_2") (pintype "input"))
    )
    (net (code "136") (name "ROW2_R") (class "Default")
      (node (ref "R219") (pin "1") (pinfunction "1_1") (pintype "input"))
      (node (ref "U101") (pin "18") (pinfunction "GPIO15_18") (pintype "bidirectional"))
    )
    (net (code "137") (name "ROW3") (class "Default")
      (node (ref "D252") (pin "1") (pinfunction "K_1") (pintype "input"))
      (node (ref "D253") (pin "1") (pinfunction "K_1") (pintype "input"))
      (node (ref "D254") (pin "1") (pinfunction "K_1") (pintype "input"))
      (node (ref "D261") (pin "1") (pinfunction "K_1") (pintype "input"))
      (node (ref "D262") (pin "1") (pinfunction "K_1") (pintype "input"))
      (node (ref "D263") (pin "1") (pinfunction "K_1") (pintype "input"))
      (node (ref "D270") (pin "1") (pinfunction "K_1") (pintype "input"))
      (node (ref "D271") (pin "1") (pinfunction "K_1") (pintype "input"))
      (node (ref "D272") (pin "1") (pinfunction "K_1") (pintype "input"))
      (node (ref "D279") (pin "1") (pinfunction "K_1") (pintype "input"))
      (node (ref "D280") (pin "1") (pinfunction "K_1") (pintype "input"))
      (node (ref "D281") (pin "1") (pinfunction "K_1") (pintype "input"))
      (node (ref "D288") (pin "1") (pinfunction "K_1") (pintype "input"))
      (node (ref "R220") (pin "2") (pinfunction "2_2") (pintype "input"))
    )
    (net (code "138") (name "ROW3_R") (class "Default")
      (node (ref "R220") (pin "1") (pinfunction "1_1") (pintype "input"))
      (node (ref "U101") (pin "27") (pinfunction "GPIO16_27") (pintype "bidirectional"))
    )
    (net (code "139") (name "ROW4") (class "Default")
      (node (ref "D255") (pin "1") (pinfunction "K_1") (pintype "input"))
      (node (ref "D256") (pin "1") (pinfunction "K_1") (pintype "input"))
      (node (ref "D257") (pin "1") (pinfunction "K_1") (pintype "input"))
      (node (ref "D264") (pin "1") (pinfunction "K_1") (pintype "input"))
      (node (ref "D265") (pin "1") (pinfunction "K_1") (pintype "input"))
      (node (ref "D266") (pin "1") (pinfunction "K_1") (pintype "input"))
      (node (ref "D273") (pin "1") (pinfunction "K_1") (pintype "input"))
      (node (ref "D274") (pin "1") (pinfunction "K_1") (pintype "input"))
      (node (ref "D275") (pin "1") (pinfunction "K_1") (pintype "input"))
      (node (ref "D282") (pin "1") (pinfunction "K_1") (pintype "input"))
      (node (ref "D283") (pin "1") (pinfunction "K_1") (pintype "input"))
      (node (ref "D284") (pin "1") (pinfunction "K_1") (pintype "input"))
      (node (ref "D289") (pin "1") (pinfunction "K_1") (pintype "input"))
      (node (ref "R221") (pin "2") (pinfunction "2_2") (pintype "input"))
    )
    (net (code "140") (name "ROW4_R") (class "Default")
      (node (ref "R221") (pin "1") (pinfunction "1_1") (pintype "input"))
      (node (ref "U101") (pin "28") (pinfunction "GPIO17_28") (pintype "bidirectional"))
    )
    (net (code "141") (name "ROW5") (class "Default")
      (node (ref "D258") (pin "1") (pinfunction "K_1") (pintype "input"))
      (node (ref "D259") (pin "1") (pinfunction "K_1") (pintype "input"))
      (node (ref "D260") (pin "1") (pinfunction "K_1") (pintype "input"))
      (node (ref "D267") (pin "1") (pinfunction "K_1") (pintype "input"))
      (node (ref "D268") (pin "1") (pinfunction "K_1") (pintype "input"))
      (node (ref "D269") (pin "1") (pinfunction "K_1") (pintype "input"))
      (node (ref "D276") (pin "1") (pinfunction "K_1") (pintype "input"))
      (node (ref "D277") (pin "1") (pinfunction "K_1") (pintype "input"))
      (node (ref "D278") (pin "1") (pinfunction "K_1") (pintype "input"))
      (node (ref "D285") (pin "1") (pinfunction "K_1") (pintype "input"))
      (node (ref "D286") (pin "1") (pinfunction "K_1") (pintype "input"))
      (node (ref "D287") (pin "1") (pinfunction "K_1") (pintype "input"))
      (node (ref "D290") (pin "1") (pinfunction "K_1") (pintype "input"))
      (node (ref "R222") (pin "2") (pinfunction "2_2") (pintype "input"))
    )
    (net (code "142") (name "ROW5_R") (class "Default")
      (node (ref "R222") (pin "1") (pinfunction "1_1") (pintype "input"))
      (node (ref "U101") (pin "29") (pinfunction "GPIO18_29") (pintype "bidirectional"))
    )
    (net (code "143") (name "RS") (class "Default")
      (node (ref "FPC1") (pin "3") (pinfunction "3_3") (pintype "unspecified"))
      (node (ref "U101") (pin "34") (pinfunction "GPIO22_34") (pintype "bidirectional"))
    )
    (net (code "144") (name "RSTB") (class "Default")
      (node (ref "FPC1") (pin "4") (pinfunction "4_4") (pintype "unspecified"))
      (node (ref "U101") (pin "40") (pinfunction "GPIO28_ADC2_40") (pintype "bidirectional"))
    )
    (net (code "145") (name "SCL") (class "Default")
      (node (ref "FPC1") (pin "2") (pinfunction "2_2") (pintype "unspecified"))
      (node (ref "U101") (pin "39") (pinfunction "GPIO27_ADC1_39") (pintype "bidirectional"))
    )
    (net (code "146") (name "SDA") (class "Default")
      (node (ref "FPC1") (pin "1") (pinfunction "1_1") (pintype "unspecified"))
      (node (ref "U101") (pin "38") (pinfunction "GPIO26_ADC0_38") (pintype "bidirectional"))
    )
    (net (code "147") (name "SWCLK") (class "Default")
      (node (ref "J102") (pin "1") (pinfunction "1_1") (pintype "input"))
      (node (ref "U101") (pin "24") (pinfunction "SWCLK_24") (pintype "output"))
    )
    (net (code "148") (name "SWDIO") (class "Default")
      (node (ref "J102") (pin "3") (pinfunction "3_3") (pintype "input"))
      (node (ref "U101") (pin "25") (pinfunction "SWD_25") (pintype "bidirectional"))
    )
    (net (code "149") (name "TE") (class "Default")
      (node (ref "FPC1") (pin "6") (pinfunction "6_6") (pintype "unspecified"))
      (node (ref "U101") (pin "41") (pinfunction "GPIO29_ADC3_41") (pintype "bidirectional"))
    )
    (net (code "150") (name "USB_N") (class "Default")
      (node (ref "R109") (pin "2") (pinfunction "2_2") (pintype "input"))
      (node (ref "U101") (pin "46") (pinfunction "USB_DM_46") (pintype "bidirectional"))
    )
    (net (code "151") (name "USB_P") (class "Default")
      (node (ref "R111") (pin "2") (pinfunction "2_2") (pintype "input"))
      (node (ref "U101") (pin "47") (pinfunction "USB_DP_47") (pintype "bidirectional"))
    )
    (net (code "152") (name "XIN") (class "Default")
      (node (ref "C123") (pin "1") (pinfunction "1_1") (pintype "unspecified"))
      (node (ref "R120") (pin "2") (pinfunction "2_2") (pintype "input"))
      (node (ref "U101") (pin "20") (pinfunction "XIN_20") (pintype "input"))
      (node (ref "Y101") (pin "1") (pinfunction "1_1") (pintype "input"))
    )
    (net (code "153") (name "XOUT") (class "Default")
      (node (ref "R120") (pin "1") (pinfunction "1_1") (pintype "input"))
      (node (ref "R121") (pin "2") (pinfunction "2_2") (pintype "input"))
      (node (ref "U101") (pin "21") (pinfunction "XOUT_21") (pintype "unspecified"))
    )
    (net (code "154") (name "X_R") (class "Default")
      (node (ref "C124") (pin "1") (pinfunction "1_1") (pintype "unspecified"))
      (node (ref "R121") (pin "1") (pinfunction "1_1") (pintype "input"))
      (node (ref "Y101") (pin "3") (pinfunction "3_3") (pintype "input"))
    )
    (net (code "155") (name "unconnected-(ENC201-Pad1)") (class "Default")
      (node (ref "ENC201") (pin "1") (pinfunction "1_1") (pintype "input+no_connect"))
    )
    (net (code "156") (name "unconnected-(ENC201-Pad2)") (class "Default")
      (node (ref "ENC201") (pin "2") (pinfunction "2_2") (pintype "input+no_connect"))
    )
    (net (code "157") (name "unconnected-(FPC1-Pad11)") (class "Default")
      (node (ref "FPC1") (pin "11") (pinfunction "11_11") (pintype "unspecified+no_connect"))
    )
    (net (code "158") (name "unconnected-(FPC1-Pad12)") (class "Default")
      (node (ref "FPC1") (pin "12") (pinfunction "12_12") (pintype "unspecified+no_connect"))
    )
    (net (code "159") (name "unconnected-(J101-SBU1-Pad9)") (class "Default")
      (node (ref "J101") (pin "9") (pinfunction "SBU1_9") (pintype "unspecified+no_connect"))
    )
    (net (code "160") (name "unconnected-(J101-SBU2-Pad3)") (class "Default")
      (node (ref "J101") (pin "3") (pinfunction "SBU2_3") (pintype "unspecified+no_connect"))
    )
    (net (code "161") (name "unconnected-(U101-GPIO23-Pad35)") (class "Default")
      (node (ref "U101") (pin "35") (pinfunction "GPIO23_35") (pintype "bidirectional+no_connect"))
    )
    (net (code "162") (name "unconnected-(U101-GPIO24-Pad36)") (class "Default")
      (node (ref "U101") (pin "36") (pinfunction "GPIO24_36") (pintype "bidirectional+no_connect"))
    )
    (net (code "163") (name "unconnected-(U101-GPIO25-Pad37)") (class "Default")
      (node (ref "U101") (pin "37") (pinfunction "GPIO25_37") (pintype "bidirectional+no_connect"))
    )
  )
)
